# circuit.net
KiCad netlist of a schematic drawn in EAGLE
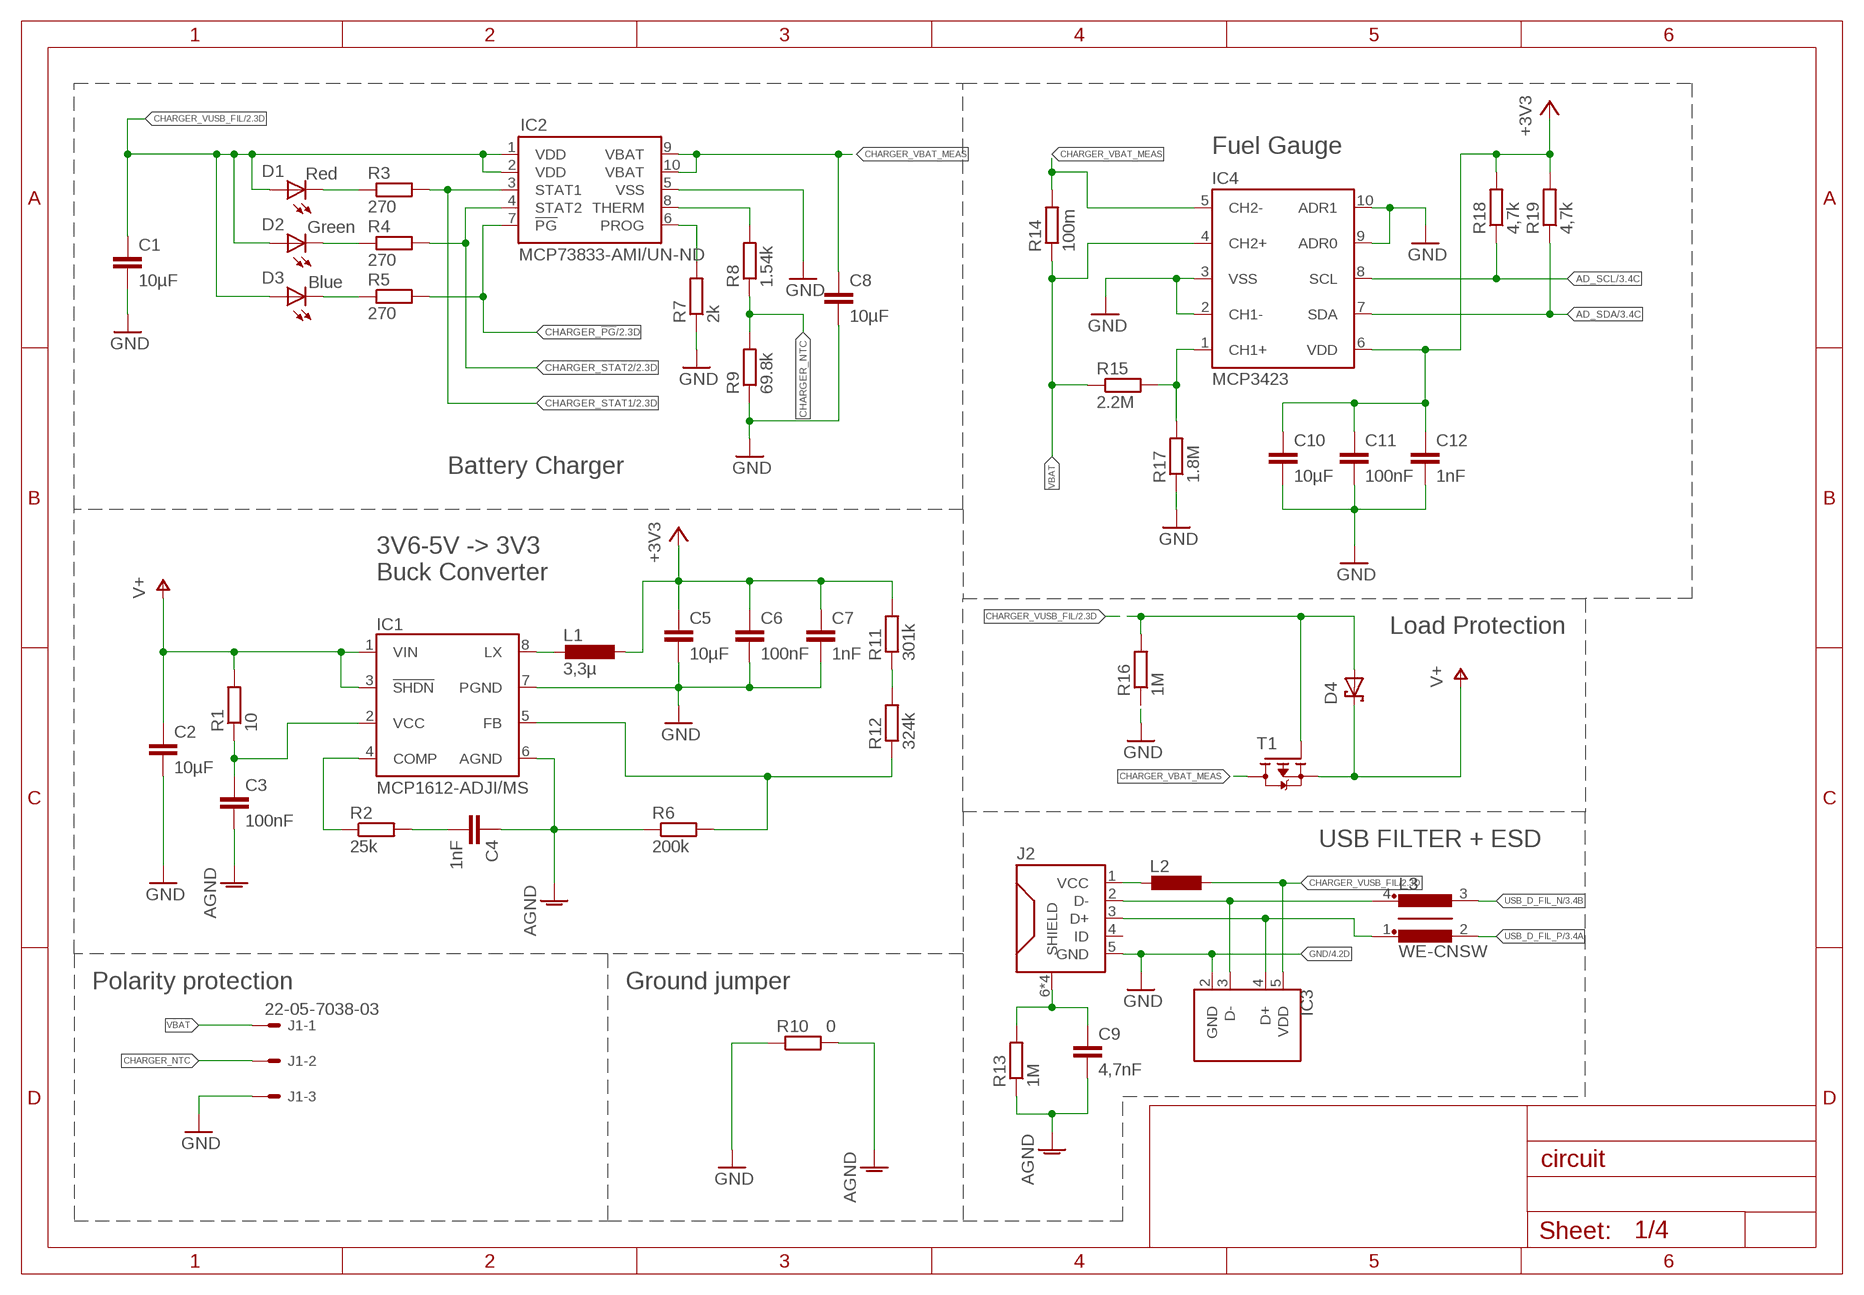
[diagram p0: schematic, sheet 1]
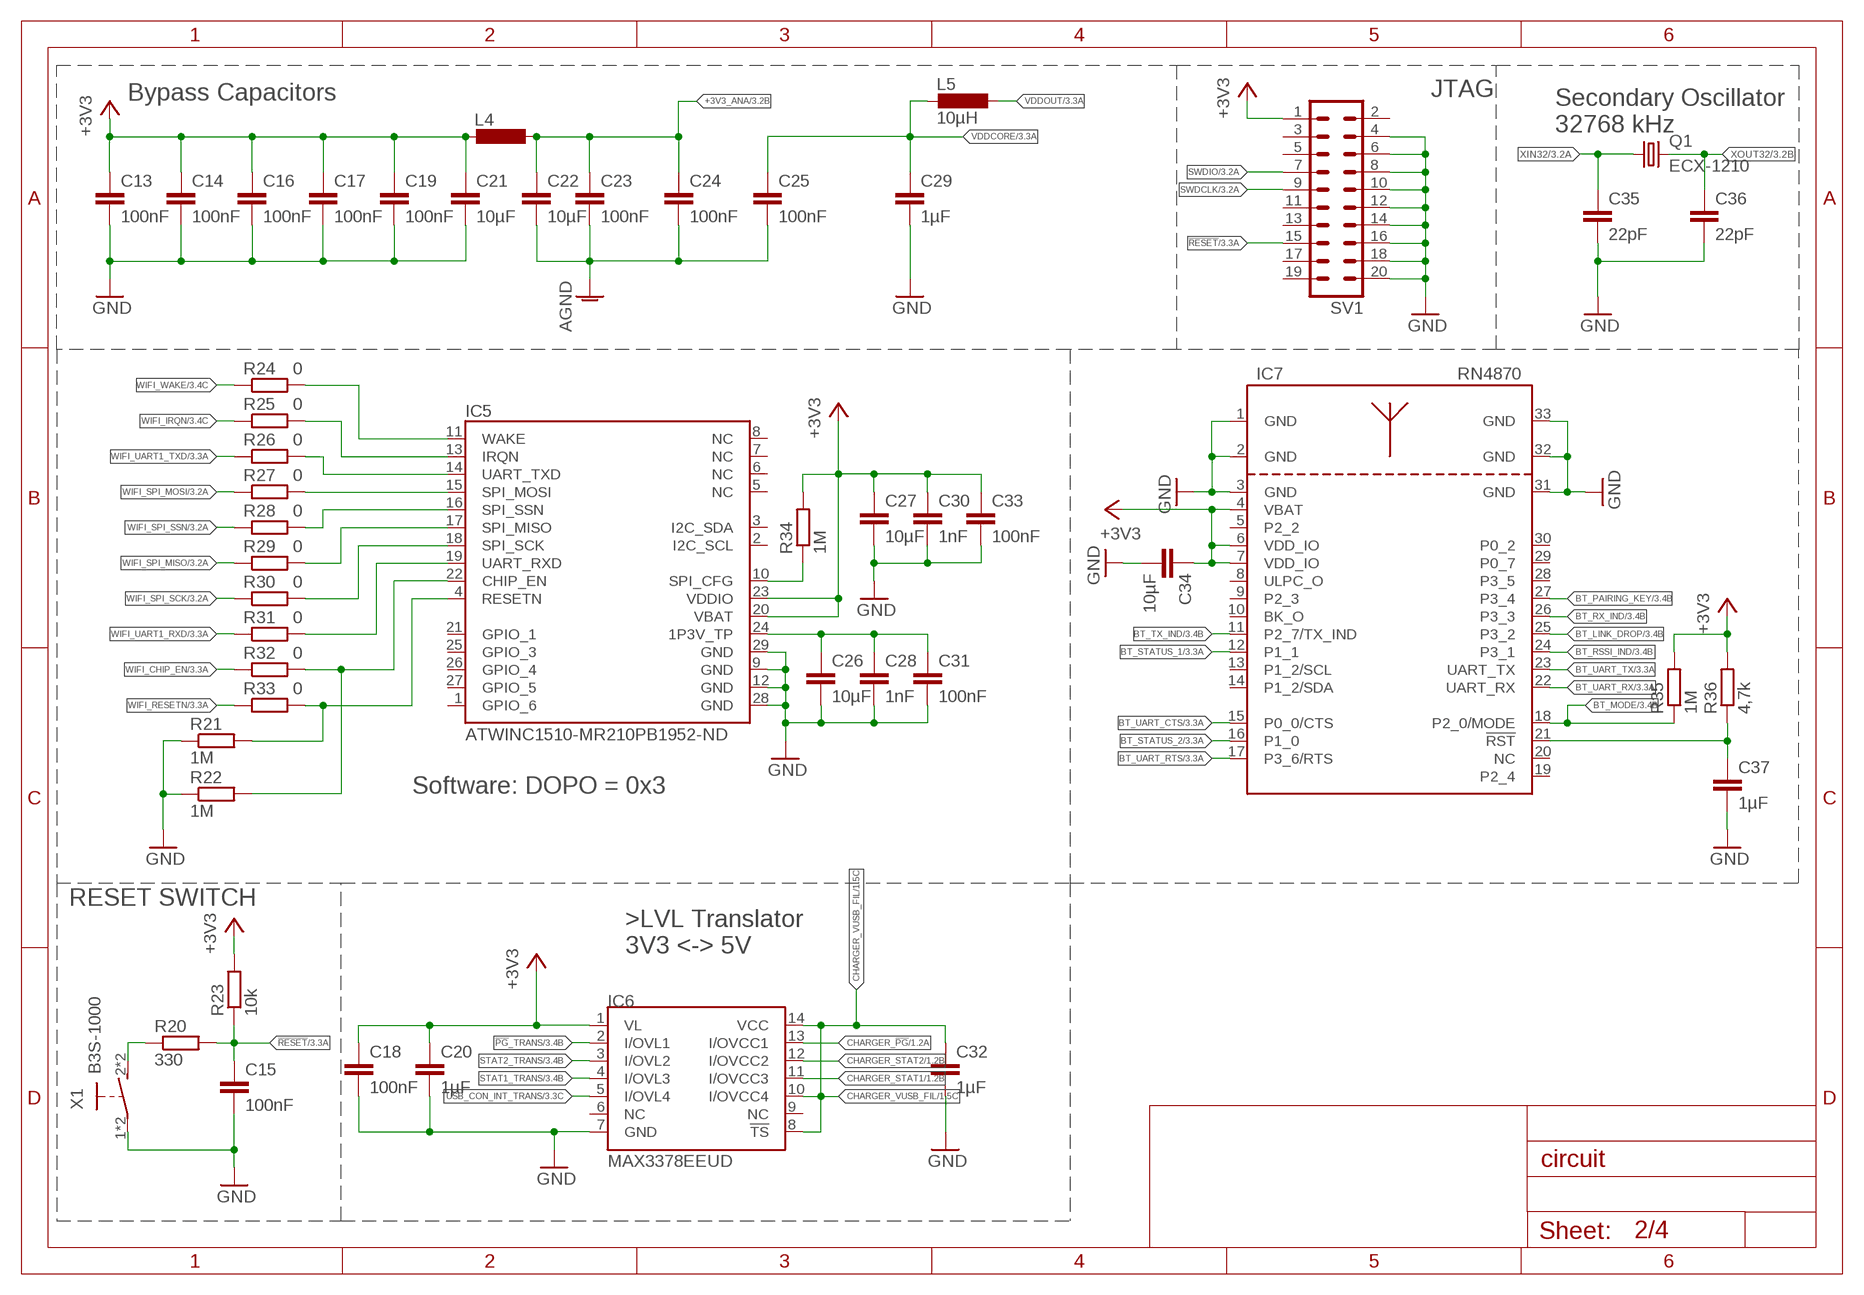
[diagram p1: schematic, sheet 2]
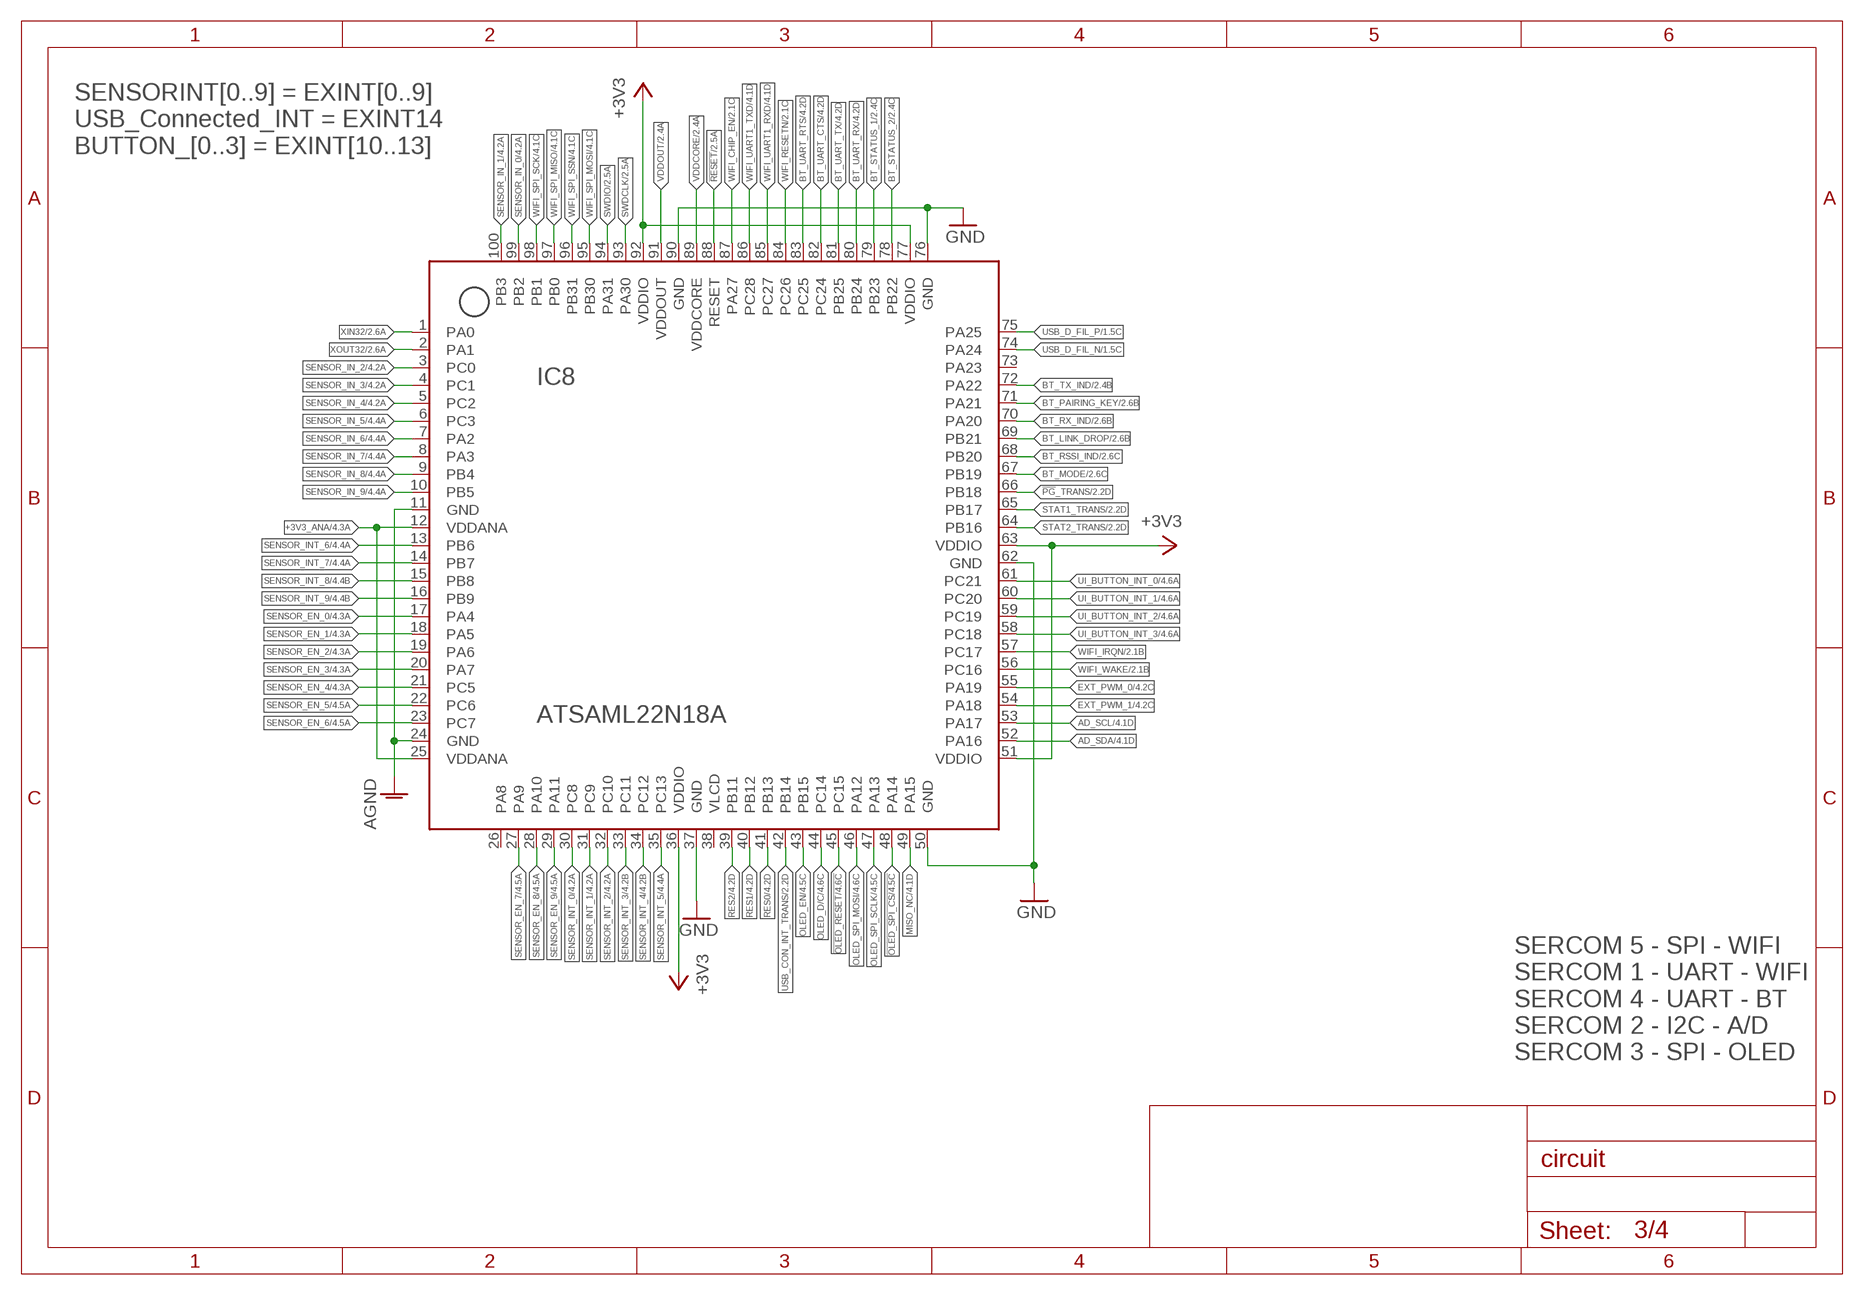
[diagram p2: schematic, sheet 3]
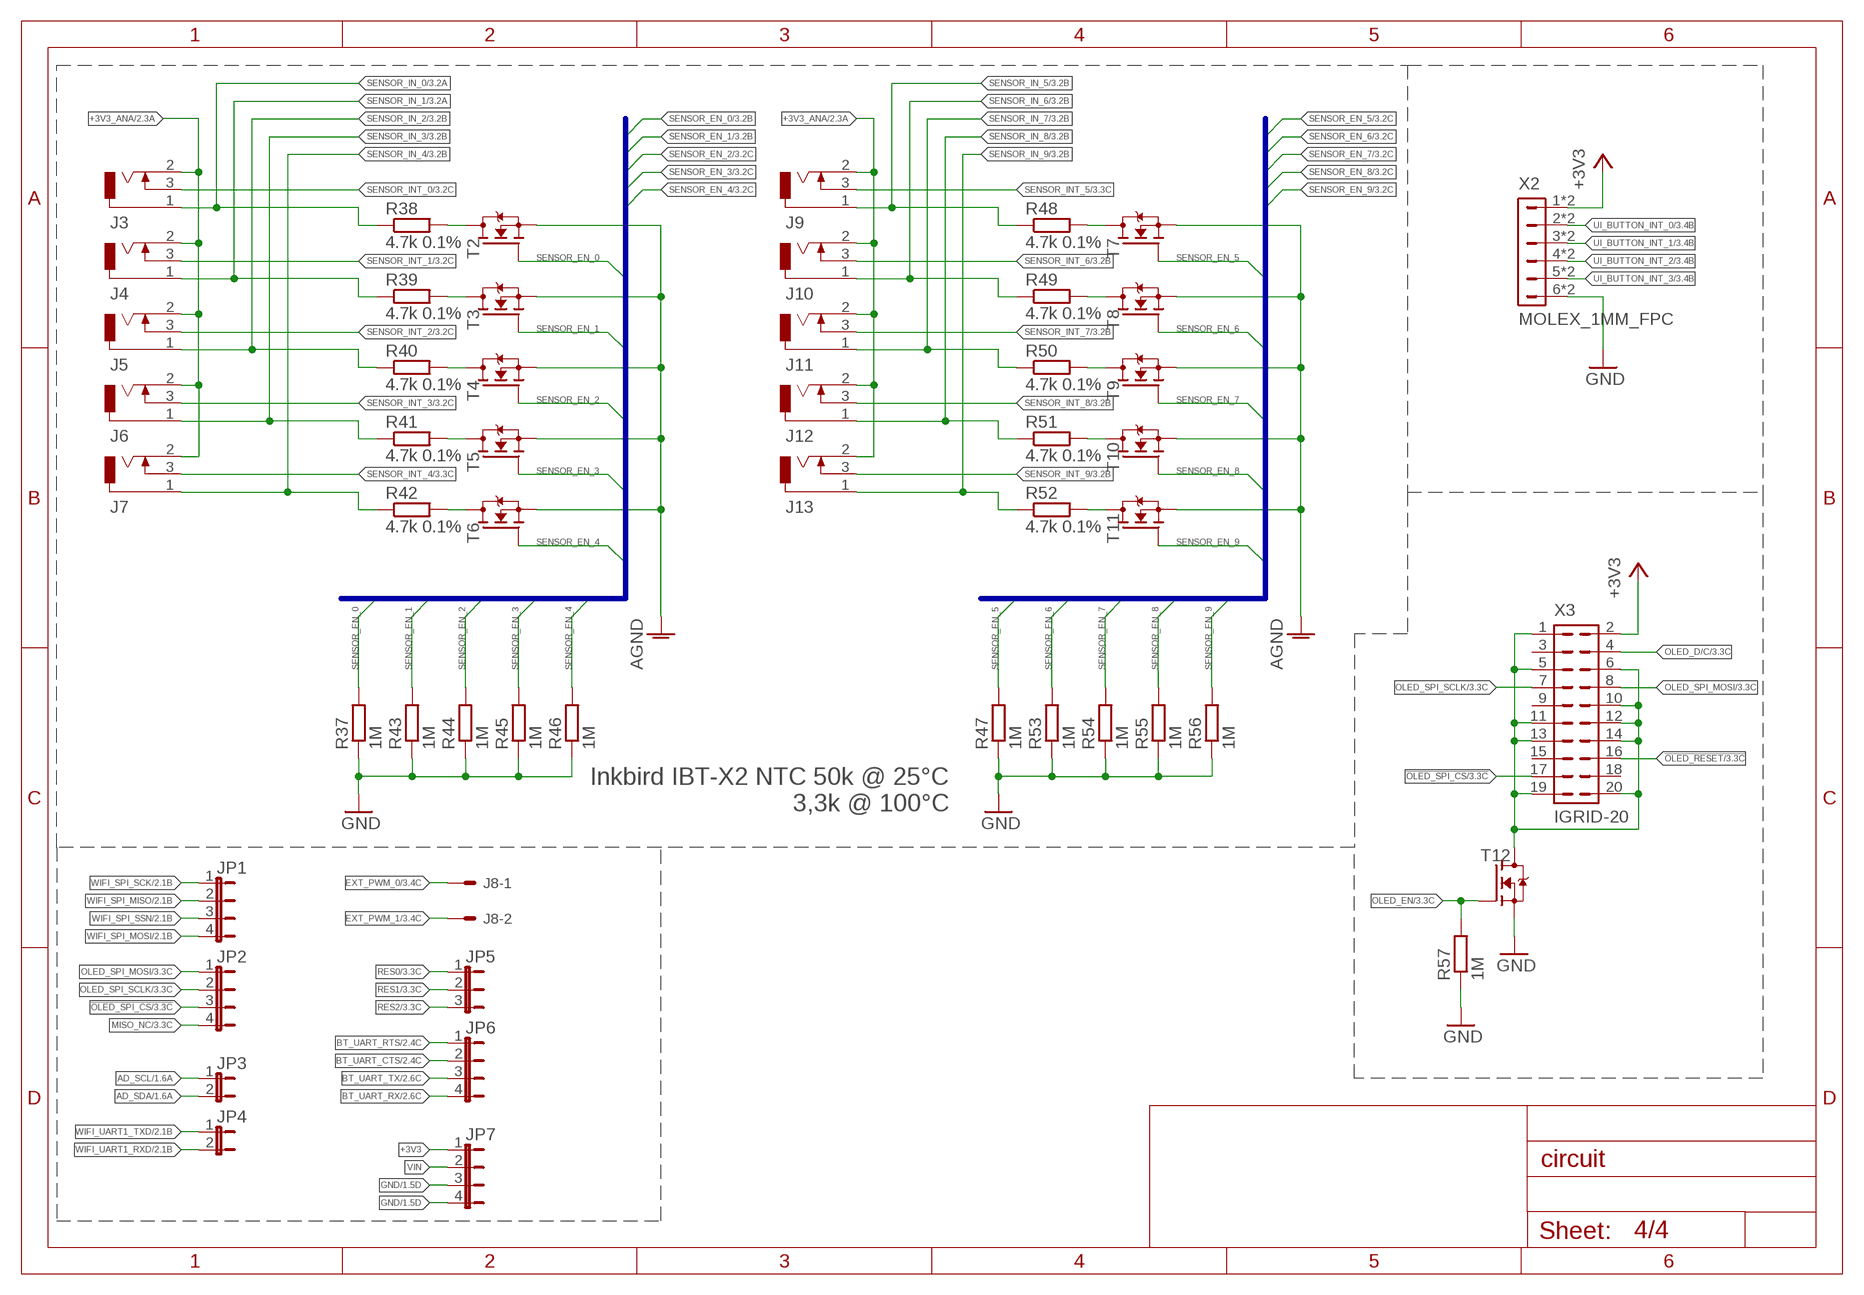
[diagram p3: schematic, sheet 4]

(export (version "E")
  (design (tool "Eeschema 10.0.6"))
  (components
    (comp (ref "J3")
      (value "2.5MM-AUDIO-JACK-MONO")
      (footprint "eagle-import:2.5MM-AUDIO-JACK-MONO")
      (libsource (lib "eagle-import") (part "2.5MM-AUDIO-JACK-MONO"))
    )
    (comp (ref "J4")
      (value "2.5MM-AUDIO-JACK-MONO")
      (footprint "eagle-import:2.5MM-AUDIO-JACK-MONO")
      (libsource (lib "eagle-import") (part "2.5MM-AUDIO-JACK-MONO"))
    )
    (comp (ref "J5")
      (value "2.5MM-AUDIO-JACK-MONO")
      (footprint "eagle-import:2.5MM-AUDIO-JACK-MONO")
      (libsource (lib "eagle-import") (part "2.5MM-AUDIO-JACK-MONO"))
    )
    (comp (ref "J6")
      (value "2.5MM-AUDIO-JACK-MONO")
      (footprint "eagle-import:2.5MM-AUDIO-JACK-MONO")
      (libsource (lib "eagle-import") (part "2.5MM-AUDIO-JACK-MONO"))
    )
    (comp (ref "J7")
      (value "2.5MM-AUDIO-JACK-MONO")
      (footprint "eagle-import:2.5MM-AUDIO-JACK-MONO")
      (libsource (lib "eagle-import") (part "2.5MM-AUDIO-JACK-MONO"))
    )
    (comp (ref "J8")
      (value "22-05-7028-02")
      (footprint "eagle-import:7395-02")
      (fields (field (name "OC_MOUSER") "538-22-05-7028"))
      (libsource (lib "eagle-import") (part "22-?-0205-7028"))
    )
    (comp (ref "J9")
      (value "2.5MM-AUDIO-JACK-MONONO_DRILL")
      (footprint "eagle-import:2.5MM-AUDIO-JACK-MONO-2")
      (libsource (lib "eagle-import") (part "2.5MM-AUDIO-JACK-MONONO_DRILL"))
    )
    (comp (ref "J10")
      (value "2.5MM-AUDIO-JACK-MONONO_DRILL")
      (footprint "eagle-import:2.5MM-AUDIO-JACK-MONO-2")
      (libsource (lib "eagle-import") (part "2.5MM-AUDIO-JACK-MONONO_DRILL"))
    )
    (comp (ref "J11")
      (value "2.5MM-AUDIO-JACK-MONONO_DRILL")
      (footprint "eagle-import:2.5MM-AUDIO-JACK-MONO-2")
      (libsource (lib "eagle-import") (part "2.5MM-AUDIO-JACK-MONONO_DRILL"))
    )
    (comp (ref "J12")
      (value "2.5MM-AUDIO-JACK-MONONO_DRILL")
      (footprint "eagle-import:2.5MM-AUDIO-JACK-MONO-2")
      (libsource (lib "eagle-import") (part "2.5MM-AUDIO-JACK-MONONO_DRILL"))
    )
    (comp (ref "J13")
      (value "2.5MM-AUDIO-JACK-MONONO_DRILL")
      (footprint "eagle-import:2.5MM-AUDIO-JACK-MONO-2")
      (libsource (lib "eagle-import") (part "2.5MM-AUDIO-JACK-MONONO_DRILL"))
    )
    (comp (ref "JP1")
      (value "4")
      (footprint "eagle-import:JP4")
      (libsource (lib "eagle-import") (part "JP4E"))
    )
    (comp (ref "JP2")
      (value "4")
      (footprint "eagle-import:JP4")
      (libsource (lib "eagle-import") (part "JP4E"))
    )
    (comp (ref "JP3")
      (value "2")
      (footprint "eagle-import:JP1")
      (libsource (lib "eagle-import") (part "JP1E"))
    )
    (comp (ref "JP4")
      (value "2")
      (footprint "eagle-import:JP1")
      (libsource (lib "eagle-import") (part "JP1E"))
    )
    (comp (ref "JP5")
      (value "3")
      (footprint "eagle-import:JP2")
      (libsource (lib "eagle-import") (part "JP2E"))
    )
    (comp (ref "JP6")
      (value "4")
      (footprint "eagle-import:JP4")
      (libsource (lib "eagle-import") (part "JP4E"))
    )
    (comp (ref "JP7")
      (value "4")
      (footprint "eagle-import:JP4")
      (libsource (lib "eagle-import") (part "JP4E"))
    )
    (comp (ref "R37")
      (value "1M")
      (footprint "eagle-import:R0603")
      (libsource (lib "eagle-import") (part "R-EU_R0603"))
    )
    (comp (ref "R38")
      (value "4.7k 0.1%")
      (footprint "eagle-import:R0603")
      (libsource (lib "eagle-import") (part "R-EU_R0603"))
    )
    (comp (ref "R39")
      (value "4.7k 0.1%")
      (footprint "eagle-import:R0603")
      (libsource (lib "eagle-import") (part "R-EU_R0603"))
    )
    (comp (ref "R40")
      (value "4.7k 0.1%")
      (footprint "eagle-import:R0603")
      (libsource (lib "eagle-import") (part "R-EU_R0603"))
    )
    (comp (ref "R41")
      (value "4.7k 0.1%")
      (footprint "eagle-import:R0603")
      (libsource (lib "eagle-import") (part "R-EU_R0603"))
    )
    (comp (ref "R42")
      (value "4.7k 0.1%")
      (footprint "eagle-import:R0603")
      (libsource (lib "eagle-import") (part "R-EU_R0603"))
    )
    (comp (ref "R43")
      (value "1M")
      (footprint "eagle-import:R0603")
      (libsource (lib "eagle-import") (part "R-EU_R0603"))
    )
    (comp (ref "R44")
      (value "1M")
      (footprint "eagle-import:R0603")
      (libsource (lib "eagle-import") (part "R-EU_R0603"))
    )
    (comp (ref "R45")
      (value "1M")
      (footprint "eagle-import:R0603")
      (libsource (lib "eagle-import") (part "R-EU_R0603"))
    )
    (comp (ref "R46")
      (value "1M")
      (footprint "eagle-import:R0603")
      (libsource (lib "eagle-import") (part "R-EU_R0603"))
    )
    (comp (ref "R47")
      (value "1M")
      (footprint "eagle-import:R0603")
      (libsource (lib "eagle-import") (part "R-EU_R0603"))
    )
    (comp (ref "R48")
      (value "4.7k 0.1%")
      (footprint "eagle-import:R0603")
      (libsource (lib "eagle-import") (part "R-EU_R0603"))
    )
    (comp (ref "R49")
      (value "4.7k 0.1%")
      (footprint "eagle-import:R0603")
      (libsource (lib "eagle-import") (part "R-EU_R0603"))
    )
    (comp (ref "R50")
      (value "4.7k 0.1%")
      (footprint "eagle-import:R0603")
      (libsource (lib "eagle-import") (part "R-EU_R0603"))
    )
    (comp (ref "R51")
      (value "4.7k 0.1%")
      (footprint "eagle-import:R0603")
      (libsource (lib "eagle-import") (part "R-EU_R0603"))
    )
    (comp (ref "R52")
      (value "4.7k 0.1%")
      (footprint "eagle-import:R0603")
      (libsource (lib "eagle-import") (part "R-EU_R0603"))
    )
    (comp (ref "R53")
      (value "1M")
      (footprint "eagle-import:R0603")
      (libsource (lib "eagle-import") (part "R-EU_R0603"))
    )
    (comp (ref "R54")
      (value "1M")
      (footprint "eagle-import:R0603")
      (libsource (lib "eagle-import") (part "R-EU_R0603"))
    )
    (comp (ref "R55")
      (value "1M")
      (footprint "eagle-import:R0603")
      (libsource (lib "eagle-import") (part "R-EU_R0603"))
    )
    (comp (ref "R56")
      (value "1M")
      (footprint "eagle-import:R0603")
      (libsource (lib "eagle-import") (part "R-EU_R0603"))
    )
    (comp (ref "R57")
      (value "1M")
      (footprint "eagle-import:R0603")
      (libsource (lib "eagle-import") (part "R-EU_R0603"))
    )
    (comp (ref "T2")
      (value "NMOSSOT323")
      (footprint "eagle-import:SOT-323")
      (libsource (lib "eagle-import") (part "NMOSSOT323"))
    )
    (comp (ref "T3")
      (value "NMOSSOT323")
      (footprint "eagle-import:SOT-323")
      (libsource (lib "eagle-import") (part "NMOSSOT323"))
    )
    (comp (ref "T4")
      (value "NMOSSOT323")
      (footprint "eagle-import:SOT-323")
      (libsource (lib "eagle-import") (part "NMOSSOT323"))
    )
    (comp (ref "T5")
      (value "NMOSSOT323")
      (footprint "eagle-import:SOT-323")
      (libsource (lib "eagle-import") (part "NMOSSOT323"))
    )
    (comp (ref "T6")
      (value "NMOSSOT323")
      (footprint "eagle-import:SOT-323")
      (libsource (lib "eagle-import") (part "NMOSSOT323"))
    )
    (comp (ref "T7")
      (value "NMOSSOT323")
      (footprint "eagle-import:SOT-323")
      (libsource (lib "eagle-import") (part "NMOSSOT323"))
    )
    (comp (ref "T8")
      (value "NMOSSOT323")
      (footprint "eagle-import:SOT-323")
      (libsource (lib "eagle-import") (part "NMOSSOT323"))
    )
    (comp (ref "T9")
      (value "NMOSSOT323")
      (footprint "eagle-import:SOT-323")
      (libsource (lib "eagle-import") (part "NMOSSOT323"))
    )
    (comp (ref "T10")
      (value "NMOSSOT323")
      (footprint "eagle-import:SOT-323")
      (libsource (lib "eagle-import") (part "NMOSSOT323"))
    )
    (comp (ref "T11")
      (value "NMOSSOT323")
      (footprint "eagle-import:SOT-323")
      (libsource (lib "eagle-import") (part "NMOSSOT323"))
    )
    (comp (ref "T12")
      (value "NMOSSOT323")
      (footprint "eagle-import:SOT-323")
      (libsource (lib "eagle-import") (part "NMOSSOT323"))
    )
    (comp (ref "X2")
      (value "MOLEX_1MM_FPC")
      (footprint "eagle-import:1MM_FPC_ZIF")
      (libsource (lib "eagle-import") (part "MOLEX_1MM_FPC"))
    )
    (comp (ref "X3")
      (value "IGRID-20")
      (footprint "eagle-import:I-GRID-20")
      (libsource (lib "eagle-import") (part "IGRID-20"))
    )
    (comp (ref "C13")
      (value "100nF")
      (footprint "eagle-import:C0603")
      (libsource (lib "eagle-import") (part "C-EUC0603"))
    )
    (comp (ref "C14")
      (value "100nF")
      (footprint "eagle-import:C0603")
      (libsource (lib "eagle-import") (part "C-EUC0603"))
    )
    (comp (ref "C15")
      (value "100nF")
      (footprint "eagle-import:C0603")
      (libsource (lib "eagle-import") (part "C-EUC0603"))
    )
    (comp (ref "C16")
      (value "100nF")
      (footprint "eagle-import:C0603")
      (libsource (lib "eagle-import") (part "C-EUC0603"))
    )
    (comp (ref "C17")
      (value "100nF")
      (footprint "eagle-import:C0603")
      (libsource (lib "eagle-import") (part "C-EUC0603"))
    )
    (comp (ref "C18")
      (value "100nF")
      (footprint "eagle-import:C0603")
      (libsource (lib "eagle-import") (part "C-EUC0603"))
    )
    (comp (ref "C19")
      (value "100nF")
      (footprint "eagle-import:C0603")
      (libsource (lib "eagle-import") (part "C-EUC0603"))
    )
    (comp (ref "C20")
      (value "1µF")
      (footprint "eagle-import:C0603")
      (libsource (lib "eagle-import") (part "C-EUC0603"))
    )
    (comp (ref "C21")
      (value "10µF")
      (footprint "eagle-import:C0805")
      (libsource (lib "eagle-import") (part "C-EUC0805"))
    )
    (comp (ref "C22")
      (value "10µF")
      (footprint "eagle-import:C0805")
      (libsource (lib "eagle-import") (part "C-EUC0805"))
    )
    (comp (ref "C23")
      (value "100nF")
      (footprint "eagle-import:C0603")
      (libsource (lib "eagle-import") (part "C-EUC0603"))
    )
    (comp (ref "C24")
      (value "100nF")
      (footprint "eagle-import:C0603")
      (libsource (lib "eagle-import") (part "C-EUC0603"))
    )
    (comp (ref "C25")
      (value "100nF")
      (footprint "eagle-import:C0603")
      (libsource (lib "eagle-import") (part "C-EUC0603"))
    )
    (comp (ref "C26")
      (value "10µF")
      (footprint "eagle-import:C0805")
      (libsource (lib "eagle-import") (part "C-EUC0805"))
    )
    (comp (ref "C27")
      (value "10µF")
      (footprint "eagle-import:C0805")
      (libsource (lib "eagle-import") (part "C-EUC0805"))
    )
    (comp (ref "C28")
      (value "1nF")
      (footprint "eagle-import:C0603")
      (libsource (lib "eagle-import") (part "C-EUC0603"))
    )
    (comp (ref "C29")
      (value "1µF")
      (footprint "eagle-import:C0603")
      (libsource (lib "eagle-import") (part "C-EUC0603"))
    )
    (comp (ref "C30")
      (value "1nF")
      (footprint "eagle-import:C0603")
      (libsource (lib "eagle-import") (part "C-EUC0603"))
    )
    (comp (ref "C31")
      (value "100nF")
      (footprint "eagle-import:C0603")
      (libsource (lib "eagle-import") (part "C-EUC0603"))
    )
    (comp (ref "C32")
      (value "1µF")
      (footprint "eagle-import:C0603")
      (libsource (lib "eagle-import") (part "C-EUC0603"))
    )
    (comp (ref "C33")
      (value "100nF")
      (footprint "eagle-import:C0603")
      (libsource (lib "eagle-import") (part "C-EUC0603"))
    )
    (comp (ref "C34")
      (value "10µF")
      (footprint "eagle-import:C0805")
      (libsource (lib "eagle-import") (part "C-EUC0805"))
    )
    (comp (ref "C35")
      (value "22pF")
      (footprint "eagle-import:C0603")
      (libsource (lib "eagle-import") (part "C-EUC0603"))
    )
    (comp (ref "C36")
      (value "22pF")
      (footprint "eagle-import:C0603")
      (libsource (lib "eagle-import") (part "C-EUC0603"))
    )
    (comp (ref "C37")
      (value "1µF")
      (footprint "eagle-import:C0603")
      (libsource (lib "eagle-import") (part "C-EUC0603"))
    )
    (comp (ref "IC5")
      (value "ATWINC1510-MR210PB1952-ND")
      (footprint "eagle-import:ATWINC15X0-MODULE")
      (libsource (lib "eagle-import") (part "ATWINC1510-MR210PB1952-ND"))
    )
    (comp (ref "IC6")
      (value "MAX3378EEUD")
      (footprint "eagle-import:TSSOP14")
      (libsource (lib "eagle-import") (part "MAX3378EEUD"))
    )
    (comp (ref "IC7")
      (value "RN4870")
      (footprint "eagle-import:RN4870-MODULE")
      (libsource (lib "eagle-import") (part "RN4870"))
    )
    (comp (ref "L4")
      (value "L-0603")
      (footprint "eagle-import:L0603")
      (libsource (lib "eagle-import") (part "L-0603"))
    )
    (comp (ref "L5")
      (value "10µH")
      (footprint "eagle-import:L-1210")
      (libsource (lib "eagle-import") (part "L-1210"))
    )
    (comp (ref "Q1")
      (value "ECX-1210")
      (footprint "eagle-import:ECX-1210")
      (libsource (lib "eagle-import") (part "ECX-1210"))
    )
    (comp (ref "R20")
      (value "330")
      (footprint "eagle-import:R0603")
      (libsource (lib "eagle-import") (part "R-EU_R0603"))
    )
    (comp (ref "R21")
      (value "1M")
      (footprint "eagle-import:R0603")
      (libsource (lib "eagle-import") (part "R-EU_R0603"))
    )
    (comp (ref "R22")
      (value "1M")
      (footprint "eagle-import:R0603")
      (libsource (lib "eagle-import") (part "R-EU_R0603"))
    )
    (comp (ref "R23")
      (value "10k")
      (footprint "eagle-import:R0603")
      (libsource (lib "eagle-import") (part "R-EU_R0603"))
    )
    (comp (ref "R24")
      (value "0")
      (footprint "eagle-import:R0603")
      (libsource (lib "eagle-import") (part "R-EU_R0603"))
    )
    (comp (ref "R25")
      (value "0")
      (footprint "eagle-import:R0603")
      (libsource (lib "eagle-import") (part "R-EU_R0603"))
    )
    (comp (ref "R26")
      (value "0")
      (footprint "eagle-import:R0603")
      (libsource (lib "eagle-import") (part "R-EU_R0603"))
    )
    (comp (ref "R27")
      (value "0")
      (footprint "eagle-import:R0603")
      (libsource (lib "eagle-import") (part "R-EU_R0603"))
    )
    (comp (ref "R28")
      (value "0")
      (footprint "eagle-import:R0603")
      (libsource (lib "eagle-import") (part "R-EU_R0603"))
    )
    (comp (ref "R29")
      (value "0")
      (footprint "eagle-import:R0603")
      (libsource (lib "eagle-import") (part "R-EU_R0603"))
    )
    (comp (ref "R30")
      (value "0")
      (footprint "eagle-import:R0603")
      (libsource (lib "eagle-import") (part "R-EU_R0603"))
    )
    (comp (ref "R31")
      (value "0")
      (footprint "eagle-import:R0603")
      (libsource (lib "eagle-import") (part "R-EU_R0603"))
    )
    (comp (ref "R32")
      (value "0")
      (footprint "eagle-import:R0603")
      (libsource (lib "eagle-import") (part "R-EU_R0603"))
    )
    (comp (ref "R33")
      (value "0")
      (footprint "eagle-import:R0603")
      (libsource (lib "eagle-import") (part "R-EU_R0603"))
    )
    (comp (ref "R34")
      (value "1M")
      (footprint "eagle-import:R0603")
      (libsource (lib "eagle-import") (part "R-EU_R0603"))
    )
    (comp (ref "R35")
      (value "1M")
      (footprint "eagle-import:R0603")
      (libsource (lib "eagle-import") (part "R-EU_R0603"))
    )
    (comp (ref "R36")
      (value "4,7k")
      (footprint "eagle-import:R0603")
      (libsource (lib "eagle-import") (part "R-EU_R0603"))
    )
    (comp (ref "SV1")
      (value "JTAGEDU")
      (footprint "eagle-import:ML20")
      (libsource (lib "eagle-import") (part "ML20"))
    )
    (comp (ref "X1")
      (value "B3S-1000")
      (footprint "eagle-import:B3S")
      (libsource (lib "eagle-import") (part "B3S-1000"))
    )
    (comp (ref "IC8")
      (value "ATSAML22N18A")
      (footprint "eagle-import:TQFP100")
      (libsource (lib "eagle-import") (part "ATSAML22N18A"))
    )
    (comp (ref "C1")
      (value "10µF")
      (footprint "eagle-import:C0805")
      (libsource (lib "eagle-import") (part "C-EUC0805"))
    )
    (comp (ref "C2")
      (value "10µF")
      (footprint "eagle-import:C0805")
      (libsource (lib "eagle-import") (part "C-EUC0805"))
    )
    (comp (ref "C3")
      (value "100nF")
      (footprint "eagle-import:C0603")
      (libsource (lib "eagle-import") (part "C-EUC0603"))
    )
    (comp (ref "C4")
      (value "1nF")
      (footprint "eagle-import:C0603")
      (libsource (lib "eagle-import") (part "C-EUC0603"))
    )
    (comp (ref "C5")
      (value "10µF")
      (footprint "eagle-import:C0805")
      (libsource (lib "eagle-import") (part "C-EUC0805"))
    )
    (comp (ref "C6")
      (value "100nF")
      (footprint "eagle-import:C0603")
      (libsource (lib "eagle-import") (part "C-EUC0603"))
    )
    (comp (ref "C7")
      (value "1nF")
      (footprint "eagle-import:C0603")
      (libsource (lib "eagle-import") (part "C-EUC0603"))
    )
    (comp (ref "C8")
      (value "10µF")
      (footprint "eagle-import:C0805")
      (libsource (lib "eagle-import") (part "C-EUC0805"))
    )
    (comp (ref "C9")
      (value "4,7nF")
      (footprint "eagle-import:C0603")
      (libsource (lib "eagle-import") (part "C-EUC0603"))
    )
    (comp (ref "C10")
      (value "10µF")
      (footprint "eagle-import:C0805")
      (libsource (lib "eagle-import") (part "C-EUC0805"))
    )
    (comp (ref "C11")
      (value "100nF")
      (footprint "eagle-import:C0603")
      (libsource (lib "eagle-import") (part "C-EUC0603"))
    )
    (comp (ref "C12")
      (value "1nF")
      (footprint "eagle-import:C0603")
      (libsource (lib "eagle-import") (part "C-EUC0603"))
    )
    (comp (ref "D1")
      (value "Red")
      (footprint "eagle-import:LED_2012")
      (libsource (lib "eagle-import") (part "LED-2012"))
    )
    (comp (ref "D2")
      (value "Green")
      (footprint "eagle-import:LED_2012")
      (libsource (lib "eagle-import") (part "LED-2012"))
    )
    (comp (ref "D3")
      (value "Blue")
      (footprint "eagle-import:LED_2012")
      (libsource (lib "eagle-import") (part "LED-2012"))
    )
    (comp (ref "D4")
      (value "BAT60AE6327HTSA1")
      (footprint "eagle-import:SOD323")
      (libsource (lib "eagle-import") (part "BAT60AE6327HTSA1"))
    )
    (comp (ref "IC1")
      (value "MCP1612-ADJI/MS")
      (footprint "eagle-import:MSOP8")
      (libsource (lib "eagle-import") (part "MCP1612-ADJI/MS"))
    )
    (comp (ref "IC2")
      (value "MCP73833-AMI/UN-ND")
      (footprint "eagle-import:MSOP10")
      (libsource (lib "eagle-import") (part "MCP73833-AMI/UN-ND"))
    )
    (comp (ref "IC3")
      (value "WE-TVS")
      (footprint "eagle-import:SOT23-5L")
      (libsource (lib "eagle-import") (part "WE-TVS"))
    )
    (comp (ref "IC4")
      (value "MCP3423")
      (footprint "eagle-import:MSOP10")
      (libsource (lib "eagle-import") (part "MCP3423"))
    )
    (comp (ref "J1")
      (value "22-05-7038-03")
      (footprint "eagle-import:7395-03")
      (libsource (lib "eagle-import") (part "22-?-0305-7038"))
    )
    (comp (ref "J2")
      (value "USB2-MICRO")
      (footprint "eagle-import:USB-2-MICRO")
      (libsource (lib "eagle-import") (part "USB2-MICRO"))
    )
    (comp (ref "L1")
      (value "3,3µ")
      (footprint "eagle-import:WE-LHMI")
      (libsource (lib "eagle-import") (part "WE-LHMI"))
    )
    (comp (ref "L2")
      (value "L-0603")
      (footprint "eagle-import:L0603")
      (libsource (lib "eagle-import") (part "L-0603"))
    )
    (comp (ref "L3")
      (value "WE-CNSW")
      (footprint "eagle-import:WE-CNSW")
      (libsource (lib "eagle-import") (part "WE-CNSW"))
    )
    (comp (ref "R1")
      (value "10")
      (footprint "eagle-import:R0603")
      (libsource (lib "eagle-import") (part "R-EU_R0603"))
    )
    (comp (ref "R2")
      (value "25k")
      (footprint "eagle-import:R0805")
      (libsource (lib "eagle-import") (part "R-EU_R0805"))
    )
    (comp (ref "R3")
      (value "270")
      (footprint "eagle-import:R0603")
      (libsource (lib "eagle-import") (part "R-EU_R0603"))
    )
    (comp (ref "R4")
      (value "270")
      (footprint "eagle-import:R0603")
      (libsource (lib "eagle-import") (part "R-EU_R0603"))
    )
    (comp (ref "R5")
      (value "270")
      (footprint "eagle-import:R0603")
      (libsource (lib "eagle-import") (part "R-EU_R0603"))
    )
    (comp (ref "R6")
      (value "200k")
      (footprint "eagle-import:R0603")
      (libsource (lib "eagle-import") (part "R-EU_R0603"))
    )
    (comp (ref "R7")
      (value "2k")
      (footprint "eagle-import:R0603")
      (libsource (lib "eagle-import") (part "R-EU_R0603"))
    )
    (comp (ref "R8")
      (value "1.54k")
      (footprint "eagle-import:R0603")
      (libsource (lib "eagle-import") (part "R-EU_R0603"))
    )
    (comp (ref "R9")
      (value "69.8k")
      (footprint "eagle-import:R0603")
      (libsource (lib "eagle-import") (part "R-EU_R0603"))
    )
    (comp (ref "R10")
      (value "0")
      (footprint "eagle-import:R0603")
      (libsource (lib "eagle-import") (part "R-EU_R0603"))
    )
    (comp (ref "R11")
      (value "301k")
      (footprint "eagle-import:R0603")
      (libsource (lib "eagle-import") (part "R-EU_R0603"))
    )
    (comp (ref "R12")
      (value "324k")
      (footprint "eagle-import:R0603")
      (libsource (lib "eagle-import") (part "R-EU_R0603"))
    )
    (comp (ref "R13")
      (value "1M")
      (footprint "eagle-import:R0603")
      (libsource (lib "eagle-import") (part "R-EU_R0603"))
    )
    (comp (ref "R14")
      (value "100m")
      (footprint "eagle-import:R5025")
      (libsource (lib "eagle-import") (part "R-EU_R5025"))
    )
    (comp (ref "R15")
      (value "2.2M")
      (footprint "eagle-import:R0603")
      (libsource (lib "eagle-import") (part "R-EU_R0603"))
    )
    (comp (ref "R16")
      (value "1M")
      (footprint "eagle-import:R0603")
      (libsource (lib "eagle-import") (part "R-EU_R0603"))
    )
    (comp (ref "R17")
      (value "1.8M")
      (footprint "eagle-import:R0603")
      (libsource (lib "eagle-import") (part "R-EU_R0603"))
    )
    (comp (ref "R18")
      (value "4,7k")
      (footprint "eagle-import:R0603")
      (libsource (lib "eagle-import") (part "R-EU_R0603"))
    )
    (comp (ref "R19")
      (value "4,7k")
      (footprint "eagle-import:R0603")
      (libsource (lib "eagle-import") (part "R-EU_R0603"))
    )
    (comp (ref "T1")
      (value "PMOS")
      (footprint "eagle-import:SOT23")
      (libsource (lib "eagle-import") (part "PMOS"))
    )
  )
  (nets
    (net (code "1") (name "+3V3") (class "Default")
      (node (ref "C10") (pin "1") (pinfunction "1_1") (pintype "passive"))
      (node (ref "C11") (pin "1") (pinfunction "1_1") (pintype "passive"))
      (node (ref "C12") (pin "1") (pinfunction "1_1") (pintype "passive"))
      (node (ref "C13") (pin "1") (pinfunction "1_1") (pintype "passive"))
      (node (ref "C14") (pin "1") (pinfunction "1_1") (pintype "passive"))
      (node (ref "C16") (pin "1") (pinfunction "1_1") (pintype "passive"))
      (node (ref "C17") (pin "1") (pinfunction "1_1") (pintype "passive"))
      (node (ref "C18") (pin "1") (pinfunction "1_1") (pintype "passive"))
      (node (ref "C19") (pin "1") (pinfunction "1_1") (pintype "passive"))
      (node (ref "C20") (pin "1") (pinfunction "1_1") (pintype "passive"))
      (node (ref "C21") (pin "1") (pinfunction "1_1") (pintype "passive"))
      (node (ref "C27") (pin "1") (pinfunction "1_1") (pintype "passive"))
      (node (ref "C30") (pin "1") (pinfunction "1_1") (pintype "passive"))
      (node (ref "C33") (pin "1") (pinfunction "1_1") (pintype "passive"))
      (node (ref "C34") (pin "1") (pinfunction "1_1") (pintype "passive"))
      (node (ref "C5") (pin "1") (pinfunction "1_1") (pintype "passive"))
      (node (ref "C6") (pin "1") (pinfunction "1_1") (pintype "passive"))
      (node (ref "C7") (pin "1") (pinfunction "1_1") (pintype "passive"))
      (node (ref "IC4") (pin "6") (pinfunction "VDD_6") (pintype "bidirectional"))
      (node (ref "IC5") (pin "20") (pinfunction "VBAT_20") (pintype "bidirectional"))
      (node (ref "IC5") (pin "23") (pinfunction "VDDIO_23") (pintype "bidirectional"))
      (node (ref "IC6") (pin "1") (pinfunction "VL_1") (pintype "bidirectional"))
      (node (ref "IC7") (pin "4") (pinfunction "VBAT_4") (pintype "bidirectional"))
      (node (ref "IC7") (pin "6") (pinfunction "VDD_IO_6") (pintype "bidirectional"))
      (node (ref "IC7") (pin "7") (pinfunction "VDD_IO_7") (pintype "bidirectional"))
      (node (ref "IC8") (pin "36") (pinfunction "VDDIO_36") (pintype "bidirectional"))
      (node (ref "IC8") (pin "51") (pinfunction "VDDIO_51") (pintype "bidirectional"))
      (node (ref "IC8") (pin "63") (pinfunction "VDDIO_63") (pintype "bidirectional"))
      (node (ref "IC8") (pin "77") (pinfunction "VDDIO_77") (pintype "bidirectional"))
      (node (ref "IC8") (pin "92") (pinfunction "VDDIO_92") (pintype "bidirectional"))
      (node (ref "JP7") (pin "1") (pinfunction "1_1") (pintype "passive"))
      (node (ref "L1") (pin "1") (pinfunction "1_1") (pintype "passive"))
      (node (ref "L4") (pin "2") (pinfunction "2_2") (pintype "passive"))
      (node (ref "R11") (pin "2") (pinfunction "2_2") (pintype "passive"))
      (node (ref "R18") (pin "2") (pinfunction "2_2") (pintype "passive"))
      (node (ref "R19") (pin "2") (pinfunction "2_2") (pintype "passive"))
      (node (ref "R23") (pin "2") (pinfunction "2_2") (pintype "passive"))
      (node (ref "R34") (pin "2") (pinfunction "2_2") (pintype "passive"))
      (node (ref "R35") (pin "2") (pinfunction "2_2") (pintype "passive"))
      (node (ref "R36") (pin "2") (pinfunction "2_2") (pintype "passive"))
      (node (ref "SV1") (pin "1") (pinfunction "1_1") (pintype "passive"))
      (node (ref "X2") (pin "1") (pinfunction "1_1") (pintype "passive"))
      (node (ref "X2") (pin "7") (pinfunction "1_7") (pintype "passive"))
      (node (ref "X3") (pin "2") (pinfunction "2_2") (pintype "passive"))
    )
    (net (code "2") (name "+3V3_ANA") (class "Default")
      (node (ref "C22") (pin "1") (pinfunction "1_1") (pintype "passive"))
      (node (ref "C23") (pin "1") (pinfunction "1_1") (pintype "passive"))
      (node (ref "C24") (pin "1") (pinfunction "1_1") (pintype "passive"))
      (node (ref "IC8") (pin "12") (pinfunction "VDDANA_12") (pintype "bidirectional"))
      (node (ref "IC8") (pin "25") (pinfunction "VDDANA_25") (pintype "bidirectional"))
      (node (ref "J10") (pin "2") (pinfunction "2_2") (pintype "passive"))
      (node (ref "J11") (pin "2") (pinfunction "2_2") (pintype "passive"))
      (node (ref "J12") (pin "2") (pinfunction "2_2") (pintype "passive"))
      (node (ref "J13") (pin "2") (pinfunction "2_2") (pintype "passive"))
      (node (ref "J3") (pin "2") (pinfunction "2_2") (pintype "passive"))
      (node (ref "J4") (pin "2") (pinfunction "2_2") (pintype "passive"))
      (node (ref "J5") (pin "2") (pinfunction "2_2") (pintype "passive"))
      (node (ref "J6") (pin "2") (pinfunction "2_2") (pintype "passive"))
      (node (ref "J7") (pin "2") (pinfunction "2_2") (pintype "passive"))
      (node (ref "J9") (pin "2") (pinfunction "2_2") (pintype "passive"))
      (node (ref "L4") (pin "1") (pinfunction "1_1") (pintype "passive"))
    )
    (net (code "3") (name "AD_SCL") (class "Default")
      (node (ref "IC4") (pin "8") (pinfunction "SCL_8") (pintype "bidirectional"))
      (node (ref "IC8") (pin "53") (pinfunction "PA17_53") (pintype "bidirectional"))
      (node (ref "JP3") (pin "1") (pinfunction "1_1") (pintype "passive"))
      (node (ref "R18") (pin "1") (pinfunction "1_1") (pintype "passive"))
    )
    (net (code "4") (name "AD_SDA") (class "Default")
      (node (ref "IC4") (pin "7") (pinfunction "SDA_7") (pintype "bidirectional"))
      (node (ref "IC8") (pin "52") (pinfunction "PA16_52") (pintype "bidirectional"))
      (node (ref "JP3") (pin "2") (pinfunction "2_2") (pintype "passive"))
      (node (ref "R19") (pin "1") (pinfunction "1_1") (pintype "passive"))
    )
    (net (code "5") (name "AGND") (class "Default")
      (node (ref "C22") (pin "2") (pinfunction "2_2") (pintype "passive"))
      (node (ref "C23") (pin "2") (pinfunction "2_2") (pintype "passive"))
      (node (ref "C24") (pin "2") (pinfunction "2_2") (pintype "passive"))
      (node (ref "C25") (pin "2") (pinfunction "2_2") (pintype "passive"))
      (node (ref "C3") (pin "2") (pinfunction "2_2") (pintype "passive"))
      (node (ref "C4") (pin "1") (pinfunction "1_1") (pintype "passive"))
      (node (ref "C9") (pin "2") (pinfunction "2_2") (pintype "passive"))
      (node (ref "IC1") (pin "6") (pinfunction "AGND_6") (pintype "bidirectional"))
      (node (ref "IC8") (pin "11") (pinfunction "GND_11") (pintype "power_in"))
      (node (ref "IC8") (pin "24") (pinfunction "GND_24") (pintype "power_in"))
      (node (ref "R10") (pin "2") (pinfunction "2_2") (pintype "passive"))
      (node (ref "R13") (pin "1") (pinfunction "1_1") (pintype "passive"))
      (node (ref "R6") (pin "1") (pinfunction "1_1") (pintype "passive"))
      (node (ref "T10") (pin "2") (pinfunction "S_2") (pintype "passive"))
      (node (ref "T11") (pin "2") (pinfunction "S_2") (pintype "passive"))
      (node (ref "T2") (pin "2") (pinfunction "S_2") (pintype "passive"))
      (node (ref "T3") (pin "2") (pinfunction "S_2") (pintype "passive"))
      (node (ref "T4") (pin "2") (pinfunction "S_2") (pintype "passive"))
      (node (ref "T5") (pin "2") (pinfunction "S_2") (pintype "passive"))
      (node (ref "T6") (pin "2") (pinfunction "S_2") (pintype "passive"))
      (node (ref "T7") (pin "2") (pinfunction "S_2") (pintype "passive"))
      (node (ref "T8") (pin "2") (pinfunction "S_2") (pintype "passive"))
      (node (ref "T9") (pin "2") (pinfunction "S_2") (pintype "passive"))
    )
    (net (code "6") (name "BT_LINK_DROP") (class "Default")
      (node (ref "IC7") (pin "25") (pinfunction "P3_2_25") (pintype "output"))
      (node (ref "IC8") (pin "69") (pinfunction "PB21_69") (pintype "bidirectional"))
    )
    (net (code "7") (name "BT_MODE") (class "Default")
      (node (ref "IC7") (pin "18") (pinfunction "P2_0/MODE_18") (pintype "bidirectional"))
      (node (ref "IC8") (pin "67") (pinfunction "PB19_67") (pintype "bidirectional"))
      (node (ref "R35") (pin "1") (pinfunction "1_1") (pintype "passive"))
    )
    (net (code "8") (name "BT_PAIRING_KEY") (class "Default")
      (node (ref "IC7") (pin "27") (pinfunction "P3_4_27") (pintype "output"))
      (node (ref "IC8") (pin "71") (pinfunction "PA21_71") (pintype "bidirectional"))
    )
    (net (code "9") (name "BT_RSSI_IND") (class "Default")
      (node (ref "IC7") (pin "24") (pinfunction "P3_1_24") (pintype "output"))
      (node (ref "IC8") (pin "68") (pinfunction "PB20_68") (pintype "bidirectional"))
    )
    (net (code "10") (name "BT_RX_IND") (class "Default")
      (node (ref "IC7") (pin "26") (pinfunction "P3_3_26") (pintype "output"))
      (node (ref "IC8") (pin "70") (pinfunction "PA20_70") (pintype "bidirectional"))
    )
    (net (code "11") (name "BT_STATUS_1") (class "Default")
      (node (ref "IC7") (pin "12") (pinfunction "P1_1_12") (pintype "bidirectional"))
      (node (ref "IC8") (pin "79") (pinfunction "PB23_79") (pintype "bidirectional"))
    )
    (net (code "12") (name "BT_STATUS_2") (class "Default")
      (node (ref "IC7") (pin "16") (pinfunction "P1_0_16") (pintype "bidirectional"))
      (node (ref "IC8") (pin "78") (pinfunction "PB22_78") (pintype "bidirectional"))
    )
    (net (code "13") (name "BT_TX_IND") (class "Default")
      (node (ref "IC7") (pin "11") (pinfunction "P2_7/TX_IND_11") (pintype "output"))
      (node (ref "IC8") (pin "72") (pinfunction "PA22_72") (pintype "bidirectional"))
    )
    (net (code "14") (name "BT_UART_CTS") (class "Default")
      (node (ref "IC7") (pin "15") (pinfunction "P0_0/CTS_15") (pintype "bidirectional"))
      (node (ref "IC8") (pin "82") (pinfunction "PC24_82") (pintype "bidirectional"))
      (node (ref "JP6") (pin "2") (pinfunction "2_2") (pintype "passive"))
    )
    (net (code "15") (name "BT_UART_RTS") (class "Default")
      (node (ref "IC7") (pin "17") (pinfunction "P3_6/RTS_17") (pintype "bidirectional"))
      (node (ref "IC8") (pin "83") (pinfunction "PC25_83") (pintype "bidirectional"))
      (node (ref "JP6") (pin "1") (pinfunction "1_1") (pintype "passive"))
    )
    (net (code "16") (name "BT_UART_RX") (class "Default")
      (node (ref "IC7") (pin "22") (pinfunction "UART_RX_22") (pintype "bidirectional"))
      (node (ref "IC8") (pin "80") (pinfunction "PB24_80") (pintype "bidirectional"))
      (node (ref "JP6") (pin "4") (pinfunction "4_4") (pintype "passive"))
    )
    (net (code "17") (name "BT_UART_TX") (class "Default")
      (node (ref "IC7") (pin "23") (pinfunction "UART_TX_23") (pintype "output"))
      (node (ref "IC8") (pin "81") (pinfunction "PB25_81") (pintype "bidirectional"))
      (node (ref "JP6") (pin "3") (pinfunction "3_3") (pintype "passive"))
    )
    (net (code "18") (name "CHARGER_NTC") (class "Default")
      (node (ref "J1") (pin "2") (pinfunction "S_2") (pintype "passive"))
      (node (ref "R8") (pin "1") (pinfunction "1_1") (pintype "passive"))
      (node (ref "R9") (pin "2") (pinfunction "2_2") (pintype "passive"))
    )
    (net (code "19") (name "CHARGER_STAT1") (class "Default")
      (node (ref "IC2") (pin "3") (pinfunction "STAT1_3") (pintype "bidirectional"))
      (node (ref "IC6") (pin "11") (pinfunction "I/OVCC3_11") (pintype "bidirectional"))
      (node (ref "R3") (pin "2") (pinfunction "2_2") (pintype "passive"))
    )
    (net (code "20") (name "CHARGER_STAT2") (class "Default")
      (node (ref "IC2") (pin "4") (pinfunction "STAT2_4") (pintype "bidirectional"))
      (node (ref "IC6") (pin "12") (pinfunction "I/OVCC2_12") (pintype "bidirectional"))
      (node (ref "R4") (pin "2") (pinfunction "2_2") (pintype "passive"))
    )
    (net (code "21") (name "CHARGER_VBAT_MEAS") (class "Default")
      (node (ref "C8") (pin "1") (pinfunction "1_1") (pintype "passive"))
      (node (ref "IC2") (pin "10") (pinfunction "VBAT_10") (pintype "bidirectional"))
      (node (ref "IC2") (pin "9") (pinfunction "VBAT_9") (pintype "bidirectional"))
      (node (ref "IC4") (pin "5") (pinfunction "CH2-_5") (pintype "bidirectional"))
      (node (ref "R14") (pin "2") (pinfunction "2_2") (pintype "passive"))
      (node (ref "T1") (pin "3") (pinfunction "D_3") (pintype "passive"))
    )
    (net (code "22") (name "CHARGER_VUSB_FIL") (class "Default")
      (node (ref "C1") (pin "1") (pinfunction "1_1") (pintype "passive"))
      (node (ref "C32") (pin "1") (pinfunction "1_1") (pintype "passive"))
      (node (ref "D1") (pin "2") (pinfunction "A_2") (pintype "passive"))
      (node (ref "D2") (pin "2") (pinfunction "A_2") (pintype "passive"))
      (node (ref "D3") (pin "2") (pinfunction "A_2") (pintype "passive"))
      (node (ref "D4") (pin "2") (pinfunction "A_2") (pintype "passive"))
      (node (ref "IC2") (pin "1") (pinfunction "VDD_1") (pintype "bidirectional"))
      (node (ref "IC2") (pin "2") (pinfunction "VDD_2") (pintype "bidirectional"))
      (node (ref "IC3") (pin "5") (pinfunction "VDD_5") (pintype "bidirectional"))
      (node (ref "IC6") (pin "10") (pinfunction "I/OVCC4_10") (pintype "bidirectional"))
      (node (ref "IC6") (pin "14") (pinfunction "VCC_14") (pintype "bidirectional"))
      (node (ref "IC6") (pin "8") (pinfunction "~{TS}_8") (pintype "bidirectional"))
      (node (ref "L2") (pin "1") (pinfunction "1_1") (pintype "passive"))
      (node (ref "R16") (pin "2") (pinfunction "2_2") (pintype "passive"))
      (node (ref "T1") (pin "1") (pinfunction "G_1") (pintype "passive"))
    )
    (net (code "23") (name "CHARGER_~{PG}") (class "Default")
      (node (ref "IC2") (pin "7") (pinfunction "~{PG}_7") (pintype "bidirectional"))
      (node (ref "IC6") (pin "13") (pinfunction "I/OVCC1_13") (pintype "bidirectional"))
      (node (ref "R5") (pin "2") (pinfunction "2_2") (pintype "passive"))
    )
    (net (code "24") (name "EXT_PWM_0") (class "Default")
      (node (ref "IC8") (pin "55") (pinfunction "PA19_55") (pintype "bidirectional"))
      (node (ref "J8") (pin "1") (pinfunction "S_1") (pintype "passive"))
    )
    (net (code "25") (name "EXT_PWM_1") (class "Default")
      (node (ref "IC8") (pin "54") (pinfunction "PA18_54") (pintype "bidirectional"))
      (node (ref "J8") (pin "2") (pinfunction "S_2") (pintype "passive"))
    )
    (net (code "26") (name "GND") (class "Default")
      (node (ref "C1") (pin "2") (pinfunction "2_2") (pintype "passive"))
      (node (ref "C10") (pin "2") (pinfunction "2_2") (pintype "passive"))
      (node (ref "C11") (pin "2") (pinfunction "2_2") (pintype "passive"))
      (node (ref "C12") (pin "2") (pinfunction "2_2") (pintype "passive"))
      (node (ref "C13") (pin "2") (pinfunction "2_2") (pintype "passive"))
      (node (ref "C14") (pin "2") (pinfunction "2_2") (pintype "passive"))
      (node (ref "C15") (pin "2") (pinfunction "2_2") (pintype "passive"))
      (node (ref "C16") (pin "2") (pinfunction "2_2") (pintype "passive"))
      (node (ref "C17") (pin "2") (pinfunction "2_2") (pintype "passive"))
      (node (ref "C18") (pin "2") (pinfunction "2_2") (pintype "passive"))
      (node (ref "C19") (pin "2") (pinfunction "2_2") (pintype "passive"))
      (node (ref "C2") (pin "2") (pinfunction "2_2") (pintype "passive"))
      (node (ref "C20") (pin "2") (pinfunction "2_2") (pintype "passive"))
      (node (ref "C21") (pin "2") (pinfunction "2_2") (pintype "passive"))
      (node (ref "C26") (pin "2") (pinfunction "2_2") (pintype "passive"))
      (node (ref "C27") (pin "2") (pinfunction "2_2") (pintype "passive"))
      (node (ref "C28") (pin "2") (pinfunction "2_2") (pintype "passive"))
      (node (ref "C29") (pin "2") (pinfunction "2_2") (pintype "passive"))
      (node (ref "C30") (pin "2") (pinfunction "2_2") (pintype "passive"))
      (node (ref "C31") (pin "2") (pinfunction "2_2") (pintype "passive"))
      (node (ref "C32") (pin "2") (pinfunction "2_2") (pintype "passive"))
      (node (ref "C33") (pin "2") (pinfunction "2_2") (pintype "passive"))
      (node (ref "C34") (pin "2") (pinfunction "2_2") (pintype "passive"))
      (node (ref "C35") (pin "2") (pinfunction "2_2") (pintype "passive"))
      (node (ref "C36") (pin "2") (pinfunction "2_2") (pintype "passive"))
      (node (ref "C37") (pin "2") (pinfunction "2_2") (pintype "passive"))
      (node (ref "C5") (pin "2") (pinfunction "2_2") (pintype "passive"))
      (node (ref "C6") (pin "2") (pinfunction "2_2") (pintype "passive"))
      (node (ref "C7") (pin "2") (pinfunction "2_2") (pintype "passive"))
      (node (ref "C8") (pin "2") (pinfunction "2_2") (pintype "passive"))
      (node (ref "IC1") (pin "7") (pinfunction "PGND_7") (pintype "bidirectional"))
      (node (ref "IC2") (pin "5") (pinfunction "VSS_5") (pintype "bidirectional"))
      (node (ref "IC3") (pin "2") (pinfunction "GND_2") (pintype "bidirectional"))
      (node (ref "IC4") (pin "10") (pinfunction "ADR1_10") (pintype "bidirectional"))
      (node (ref "IC4") (pin "2") (pinfunction "CH1-_2") (pintype "bidirectional"))
      (node (ref "IC4") (pin "3") (pinfunction "VSS_3") (pintype "bidirectional"))
      (node (ref "IC4") (pin "9") (pinfunction "ADR0_9") (pintype "bidirectional"))
      (node (ref "IC5") (pin "12") (pinfunction "GND_12") (pintype "power_in"))
      (node (ref "IC5") (pin "28") (pinfunction "GND_28") (pintype "power_in"))
      (node (ref "IC5") (pin "29") (pinfunction "GND_29") (pintype "power_in"))
      (node (ref "IC5") (pin "9") (pinfunction "GND_9") (pintype "power_in"))
      (node (ref "IC6") (pin "7") (pinfunction "GND_7") (pintype "bidirectional"))
      (node (ref "IC7") (pin "1") (pinfunction "GND_1") (pintype "power_in"))
      (node (ref "IC7") (pin "2") (pinfunction "GND_2") (pintype "power_in"))
      (node (ref "IC7") (pin "3") (pinfunction "GND_3") (pintype "power_in"))
      (node (ref "IC7") (pin "31") (pinfunction "GND_31") (pintype "power_in"))
      (node (ref "IC7") (pin "32") (pinfunction "GND_32") (pintype "power_in"))
      (node (ref "IC7") (pin "33") (pinfunction "GND_33") (pintype "power_in"))
      (node (ref "IC8") (pin "37") (pinfunction "GND_37") (pintype "power_in"))
      (node (ref "IC8") (pin "50") (pinfunction "GND_50") (pintype "power_in"))
      (node (ref "IC8") (pin "62") (pinfunction "GND_62") (pintype "power_in"))
      (node (ref "IC8") (pin "76") (pinfunction "GND_76") (pintype "power_in"))
      (node (ref "IC8") (pin "90") (pinfunction "GND_90") (pintype "power_in"))
      (node (ref "J1") (pin "3") (pinfunction "S_3") (pintype "passive"))
      (node (ref "J2") (pin "5") (pinfunction "GND_5") (pintype "power_in"))
      (node (ref "JP7") (pin "3") (pinfunction "3_3") (pintype "passive"))
      (node (ref "JP7") (pin "4") (pinfunction "4_4") (pintype "passive"))
      (node (ref "R10") (pin "1") (pinfunction "1_1") (pintype "passive"))
      (node (ref "R16") (pin "1") (pinfunction "1_1") (pintype "passive"))
      (node (ref "R17") (pin "1") (pinfunction "1_1") (pintype "passive"))
      (node (ref "R21") (pin "1") (pinfunction "1_1") (pintype "passive"))
      (node (ref "R22") (pin "1") (pinfunction "1_1") (pintype "passive"))
      (node (ref "R37") (pin "1") (pinfunction "1_1") (pintype "passive"))
      (node (ref "R43") (pin "1") (pinfunction "1_1") (pintype "passive"))
      (node (ref "R44") (pin "1") (pinfunction "1_1") (pintype "passive"))
      (node (ref "R45") (pin "1") (pinfunction "1_1") (pintype "passive"))
      (node (ref "R46") (pin "1") (pinfunction "1_1") (pintype "passive"))
      (node (ref "R47") (pin "1") (pinfunction "1_1") (pintype "passive"))
      (node (ref "R53") (pin "1") (pinfunction "1_1") (pintype "passive"))
      (node (ref "R54") (pin "1") (pinfunction "1_1") (pintype "passive"))
      (node (ref "R55") (pin "1") (pinfunction "1_1") (pintype "passive"))
      (node (ref "R56") (pin "1") (pinfunction "1_1") (pintype "passive"))
      (node (ref "R57") (pin "1") (pinfunction "1_1") (pintype "passive"))
      (node (ref "R7") (pin "1") (pinfunction "1_1") (pintype "passive"))
      (node (ref "R9") (pin "1") (pinfunction "1_1") (pintype "passive"))
      (node (ref "SV1") (pin "10") (pinfunction "10_10") (pintype "passive"))
      (node (ref "SV1") (pin "12") (pinfunction "12_12") (pintype "passive"))
      (node (ref "SV1") (pin "14") (pinfunction "14_14") (pintype "passive"))
      (node (ref "SV1") (pin "16") (pinfunction "16_16") (pintype "passive"))
      (node (ref "SV1") (pin "18") (pinfunction "18_18") (pintype "passive"))
      (node (ref "SV1") (pin "20") (pinfunction "20_20") (pintype "passive"))
      (node (ref "SV1") (pin "4") (pinfunction "4_4") (pintype "passive"))
      (node (ref "SV1") (pin "6") (pinfunction "6_6") (pintype "passive"))
      (node (ref "SV1") (pin "8") (pinfunction "8_8") (pintype "passive"))
      (node (ref "T12") (pin "2") (pinfunction "S_2") (pintype "passive"))
      (node (ref "X1") (pin "1") (pinfunction "P_1") (pintype "passive"))
      (node (ref "X1") (pin "3") (pinfunction "P_3") (pintype "passive"))
      (node (ref "X2") (pin "12") (pinfunction "6_12") (pintype "passive"))
      (node (ref "X2") (pin "6") (pinfunction "6_6") (pintype "passive"))
    )
    (net (code "27") (name "MISO_NC") (class "Default")
      (node (ref "IC8") (pin "49") (pinfunction "PA15_49") (pintype "bidirectional"))
      (node (ref "JP2") (pin "4") (pinfunction "4_4") (pintype "passive"))
    )
    (net (code "28") (name "Net-(C4-Pad2)") (class "Default")
      (node (ref "C4") (pin "2") (pinfunction "2_2") (pintype "passive"))
      (node (ref "R2") (pin "2") (pinfunction "2_2") (pintype "passive"))
    )
    (net (code "29") (name "Net-(C9-Pad1)") (class "Default")
      (node (ref "C9") (pin "1") (pinfunction "1_1") (pintype "passive"))
      (node (ref "J2") (pin "6") (pinfunction "SHIELD_6") (pintype "bidirectional"))
      (node (ref "J2") (pin "7") (pinfunction "SHIELD_7") (pintype "bidirectional"))
      (node (ref "J2") (pin "8") (pinfunction "SHIELD_8") (pintype "bidirectional"))
      (node (ref "J2") (pin "9") (pinfunction "SHIELD_9") (pintype "bidirectional"))
      (node (ref "R13") (pin "2") (pinfunction "2_2") (pintype "passive"))
    )
    (net (code "30") (name "Net-(D1-C)") (class "Default")
      (node (ref "D1") (pin "1") (pinfunction "C_1") (pintype "passive"))
      (node (ref "R3") (pin "1") (pinfunction "1_1") (pintype "passive"))
    )
    (net (code "31") (name "Net-(D2-C)") (class "Default")
      (node (ref "D2") (pin "1") (pinfunction "C_1") (pintype "passive"))
      (node (ref "R4") (pin "1") (pinfunction "1_1") (pintype "passive"))
    )
    (net (code "32") (name "Net-(D3-C)") (class "Default")
      (node (ref "D3") (pin "1") (pinfunction "C_1") (pintype "passive"))
      (node (ref "R5") (pin "1") (pinfunction "1_1") (pintype "passive"))
    )
    (net (code "33") (name "Net-(IC1-COMP)") (class "Default")
      (node (ref "IC1") (pin "4") (pinfunction "COMP_4") (pintype "bidirectional"))
      (node (ref "R2") (pin "1") (pinfunction "1_1") (pintype "passive"))
    )
    (net (code "34") (name "Net-(IC1-FB)") (class "Default")
      (node (ref "IC1") (pin "5") (pinfunction "FB_5") (pintype "bidirectional"))
      (node (ref "R12") (pin "1") (pinfunction "1_1") (pintype "passive"))
      (node (ref "R6") (pin "2") (pinfunction "2_2") (pintype "passive"))
    )
    (net (code "35") (name "Net-(IC1-LX)") (class "Default")
      (node (ref "IC1") (pin "8") (pinfunction "LX_8") (pintype "bidirectional"))
      (node (ref "L1") (pin "2") (pinfunction "2_2") (pintype "passive"))
    )
    (net (code "36") (name "Net-(IC1-VCC)") (class "Default")
      (node (ref "C3") (pin "1") (pinfunction "1_1") (pintype "passive"))
      (node (ref "IC1") (pin "2") (pinfunction "VCC_2") (pintype "bidirectional"))
      (node (ref "R1") (pin "1") (pinfunction "1_1") (pintype "passive"))
    )
    (net (code "37") (name "Net-(IC2-PROG)") (class "Default")
      (node (ref "IC2") (pin "6") (pinfunction "PROG_6") (pintype "bidirectional"))
      (node (ref "R7") (pin "2") (pinfunction "2_2") (pintype "passive"))
    )
    (net (code "38") (name "Net-(IC2-THERM)") (class "Default")
      (node (ref "IC2") (pin "8") (pinfunction "THERM_8") (pintype "bidirectional"))
      (node (ref "R8") (pin "2") (pinfunction "2_2") (pintype "passive"))
    )
    (net (code "39") (name "Net-(IC3-D+)") (class "Default")
      (node (ref "IC3") (pin "4") (pinfunction "D+_4") (pintype "bidirectional"))
      (node (ref "J2") (pin "3") (pinfunction "D+_3") (pintype "bidirectional"))
      (node (ref "L3") (pin "1") (pinfunction "1_1") (pintype "passive"))
    )
    (net (code "40") (name "Net-(IC3-D-)") (class "Default")
      (node (ref "IC3") (pin "3") (pinfunction "D-_3") (pintype "bidirectional"))
      (node (ref "J2") (pin "2") (pinfunction "D-_2") (pintype "bidirectional"))
      (node (ref "L3") (pin "4") (pinfunction "4_4") (pintype "passive"))
    )
    (net (code "41") (name "Net-(IC4-CH1+)") (class "Default")
      (node (ref "IC4") (pin "1") (pinfunction "CH1+_1") (pintype "bidirectional"))
      (node (ref "R15") (pin "2") (pinfunction "2_2") (pintype "passive"))
      (node (ref "R17") (pin "2") (pinfunction "2_2") (pintype "passive"))
    )
    (net (code "42") (name "Net-(IC5-1P3V_TP)") (class "Default")
      (node (ref "C26") (pin "1") (pinfunction "1_1") (pintype "passive"))
      (node (ref "C28") (pin "1") (pinfunction "1_1") (pintype "passive"))
      (node (ref "C31") (pin "1") (pinfunction "1_1") (pintype "passive"))
      (node (ref "IC5") (pin "24") (pinfunction "1P3V_TP_24") (pintype "bidirectional"))
    )
    (net (code "43") (name "Net-(IC5-CHIP_EN)") (class "Default")
      (node (ref "IC5") (pin "22") (pinfunction "CHIP_EN_22") (pintype "bidirectional"))
      (node (ref "R22") (pin "2") (pinfunction "2_2") (pintype "passive"))
      (node (ref "R32") (pin "2") (pinfunction "2_2") (pintype "passive"))
    )
    (net (code "44") (name "Net-(IC5-IRQN)") (class "Default")
      (node (ref "IC5") (pin "13") (pinfunction "IRQN_13") (pintype "bidirectional"))
      (node (ref "R25") (pin "2") (pinfunction "2_2") (pintype "passive"))
    )
    (net (code "45") (name "Net-(IC5-RESETN)") (class "Default")
      (node (ref "IC5") (pin "4") (pinfunction "RESETN_4") (pintype "bidirectional"))
      (node (ref "R21") (pin "2") (pinfunction "2_2") (pintype "passive"))
      (node (ref "R33") (pin "2") (pinfunction "2_2") (pintype "passive"))
    )
    (net (code "46") (name "Net-(IC5-SPI_CFG)") (class "Default")
      (node (ref "IC5") (pin "10") (pinfunction "SPI_CFG_10") (pintype "bidirectional"))
      (node (ref "R34") (pin "1") (pinfunction "1_1") (pintype "passive"))
    )
    (net (code "47") (name "Net-(IC5-SPI_MISO)") (class "Default")
      (node (ref "IC5") (pin "17") (pinfunction "SPI_MISO_17") (pintype "bidirectional"))
      (node (ref "R29") (pin "2") (pinfunction "2_2") (pintype "passive"))
    )
    (net (code "48") (name "Net-(IC5-SPI_MOSI)") (class "Default")
      (node (ref "IC5") (pin "15") (pinfunction "SPI_MOSI_15") (pintype "bidirectional"))
      (node (ref "R27") (pin "2") (pinfunction "2_2") (pintype "passive"))
    )
    (net (code "49") (name "Net-(IC5-SPI_SCK)") (class "Default")
      (node (ref "IC5") (pin "18") (pinfunction "SPI_SCK_18") (pintype "bidirectional"))
      (node (ref "R30") (pin "2") (pinfunction "2_2") (pintype "passive"))
    )
    (net (code "50") (name "Net-(IC5-SPI_SSN)") (class "Default")
      (node (ref "IC5") (pin "16") (pinfunction "SPI_SSN_16") (pintype "bidirectional"))
      (node (ref "R28") (pin "2") (pinfunction "2_2") (pintype "passive"))
    )
    (net (code "51") (name "Net-(IC5-UART_RXD)") (class "Default")
      (node (ref "IC5") (pin "19") (pinfunction "UART_RXD_19") (pintype "bidirectional"))
      (node (ref "R31") (pin "2") (pinfunction "2_2") (pintype "passive"))
    )
    (net (code "52") (name "Net-(IC5-UART_TXD)") (class "Default")
      (node (ref "IC5") (pin "14") (pinfunction "UART_TXD_14") (pintype "bidirectional"))
      (node (ref "R26") (pin "2") (pinfunction "2_2") (pintype "passive"))
    )
    (net (code "53") (name "Net-(IC5-WAKE)") (class "Default")
      (node (ref "IC5") (pin "11") (pinfunction "WAKE_11") (pintype "bidirectional"))
      (node (ref "R24") (pin "2") (pinfunction "2_2") (pintype "passive"))
    )
    (net (code "54") (name "Net-(IC7-~{RST})") (class "Default")
      (node (ref "C37") (pin "1") (pinfunction "1_1") (pintype "passive"))
      (node (ref "IC7") (pin "21") (pinfunction "~{RST}_21") (pintype "input"))
      (node (ref "R36") (pin "1") (pinfunction "1_1") (pintype "passive"))
    )
    (net (code "55") (name "Net-(J2-VCC)") (class "Default")
      (node (ref "J2") (pin "1") (pinfunction "VCC_1") (pintype "bidirectional"))
      (node (ref "L2") (pin "2") (pinfunction "2_2") (pintype "passive"))
    )
    (net (code "56") (name "Net-(R11-Pad1)") (class "Default")
      (node (ref "R11") (pin "1") (pinfunction "1_1") (pintype "passive"))
      (node (ref "R12") (pin "2") (pinfunction "2_2") (pintype "passive"))
    )
    (net (code "57") (name "Net-(R20-Pad1)") (class "Default")
      (node (ref "R20") (pin "1") (pinfunction "1_1") (pintype "passive"))
      (node (ref "X1") (pin "2") (pinfunction "S_2") (pintype "passive"))
      (node (ref "X1") (pin "4") (pinfunction "S_4") (pintype "passive"))
    )
    (net (code "58") (name "Net-(T2-D)") (class "Default")
      (node (ref "R38") (pin "2") (pinfunction "2_2") (pintype "passive"))
      (node (ref "T2") (pin "3") (pinfunction "D_3") (pintype "passive"))
    )
    (net (code "59") (name "Net-(T3-D)") (class "Default")
      (node (ref "R39") (pin "2") (pinfunction "2_2") (pintype "passive"))
      (node (ref "T3") (pin "3") (pinfunction "D_3") (pintype "passive"))
    )
    (net (code "60") (name "Net-(T4-D)") (class "Default")
      (node (ref "R40") (pin "2") (pinfunction "2_2") (pintype "passive"))
      (node (ref "T4") (pin "3") (pinfunction "D_3") (pintype "passive"))
    )
    (net (code "61") (name "Net-(T5-D)") (class "Default")
      (node (ref "R41") (pin "2") (pinfunction "2_2") (pintype "passive"))
      (node (ref "T5") (pin "3") (pinfunction "D_3") (pintype "passive"))
    )
    (net (code "62") (name "Net-(T6-D)") (class "Default")
      (node (ref "R42") (pin "2") (pinfunction "2_2") (pintype "passive"))
      (node (ref "T6") (pin "3") (pinfunction "D_3") (pintype "passive"))
    )
    (net (code "63") (name "Net-(T7-D)") (class "Default")
      (node (ref "R48") (pin "2") (pinfunction "2_2") (pintype "passive"))
      (node (ref "T7") (pin "3") (pinfunction "D_3") (pintype "passive"))
    )
    (net (code "64") (name "Net-(T8-D)") (class "Default")
      (node (ref "R49") (pin "2") (pinfunction "2_2") (pintype "passive"))
      (node (ref "T8") (pin "3") (pinfunction "D_3") (pintype "passive"))
    )
    (net (code "65") (name "Net-(T9-D)") (class "Default")
      (node (ref "R50") (pin "2") (pinfunction "2_2") (pintype "passive"))
      (node (ref "T9") (pin "3") (pinfunction "D_3") (pintype "passive"))
    )
    (net (code "66") (name "Net-(T10-D)") (class "Default")
      (node (ref "R51") (pin "2") (pinfunction "2_2") (pintype "passive"))
      (node (ref "T10") (pin "3") (pinfunction "D_3") (pintype "passive"))
    )
    (net (code "67") (name "Net-(T11-D)") (class "Default")
      (node (ref "R52") (pin "2") (pinfunction "2_2") (pintype "passive"))
      (node (ref "T11") (pin "3") (pinfunction "D_3") (pintype "passive"))
    )
    (net (code "68") (name "Net-(T12-D)") (class "Default")
      (node (ref "T12") (pin "3") (pinfunction "D_3") (pintype "passive"))
      (node (ref "X3") (pin "1") (pinfunction "1_1") (pintype "passive"))
      (node (ref "X3") (pin "10") (pinfunction "10_10") (pintype "passive"))
      (node (ref "X3") (pin "11") (pinfunction "11_11") (pintype "passive"))
      (node (ref "X3") (pin "12") (pinfunction "12_12") (pintype "passive"))
      (node (ref "X3") (pin "13") (pinfunction "13_13") (pintype "passive"))
      (node (ref "X3") (pin "14") (pinfunction "14_14") (pintype "passive"))
      (node (ref "X3") (pin "19") (pinfunction "19_19") (pintype "passive"))
      (node (ref "X3") (pin "20") (pinfunction "20_20") (pintype "passive"))
      (node (ref "X3") (pin "5") (pinfunction "5_5") (pintype "passive"))
      (node (ref "X3") (pin "6") (pinfunction "6_6") (pintype "passive"))
    )
    (net (code "69") (name "OLED_D{slash}C") (class "Default")
      (node (ref "IC8") (pin "44") (pinfunction "PC14_44") (pintype "bidirectional"))
      (node (ref "X3") (pin "4") (pinfunction "4_4") (pintype "passive"))
    )
    (net (code "70") (name "OLED_EN") (class "Default")
      (node (ref "IC8") (pin "43") (pinfunction "PB15_43") (pintype "bidirectional"))
      (node (ref "R57") (pin "2") (pinfunction "2_2") (pintype "passive"))
      (node (ref "T12") (pin "1") (pinfunction "G_1") (pintype "passive"))
    )
    (net (code "71") (name "OLED_SPI_MOSI") (class "Default")
      (node (ref "IC8") (pin "46") (pinfunction "PA12_46") (pintype "bidirectional"))
      (node (ref "JP2") (pin "1") (pinfunction "1_1") (pintype "passive"))
      (node (ref "X3") (pin "8") (pinfunction "8_8") (pintype "passive"))
    )
    (net (code "72") (name "OLED_SPI_SCLK") (class "Default")
      (node (ref "IC8") (pin "47") (pinfunction "PA13_47") (pintype "bidirectional"))
      (node (ref "JP2") (pin "2") (pinfunction "2_2") (pintype "passive"))
      (node (ref "X3") (pin "7") (pinfunction "7_7") (pintype "passive"))
    )
    (net (code "73") (name "RES0") (class "Default")
      (node (ref "IC8") (pin "41") (pinfunction "PB13_41") (pintype "bidirectional"))
      (node (ref "JP5") (pin "1") (pinfunction "1_1") (pintype "passive"))
    )
    (net (code "74") (name "RES1") (class "Default")
      (node (ref "IC8") (pin "40") (pinfunction "PB12_40") (pintype "bidirectional"))
      (node (ref "JP5") (pin "2") (pinfunction "2_2") (pintype "passive"))
    )
    (net (code "75") (name "RES2") (class "Default")
      (node (ref "IC8") (pin "39") (pinfunction "PB11_39") (pintype "bidirectional"))
      (node (ref "JP5") (pin "3") (pinfunction "3_3") (pintype "passive"))
    )
    (net (code "76") (name "SENSOR_EN_0") (class "Default")
      (node (ref "IC8") (pin "17") (pinfunction "PA4_17") (pintype "bidirectional"))
      (node (ref "R37") (pin "2") (pinfunction "2_2") (pintype "passive"))
      (node (ref "T2") (pin "1") (pinfunction "G_1") (pintype "passive"))
    )
    (net (code "77") (name "SENSOR_EN_1") (class "Default")
      (node (ref "IC8") (pin "18") (pinfunction "PA5_18") (pintype "bidirectional"))
      (node (ref "R43") (pin "2") (pinfunction "2_2") (pintype "passive"))
      (node (ref "T3") (pin "1") (pinfunction "G_1") (pintype "passive"))
    )
    (net (code "78") (name "SENSOR_EN_2") (class "Default")
      (node (ref "IC8") (pin "19") (pinfunction "PA6_19") (pintype "bidirectional"))
      (node (ref "R44") (pin "2") (pinfunction "2_2") (pintype "passive"))
      (node (ref "T4") (pin "1") (pinfunction "G_1") (pintype "passive"))
    )
    (net (code "79") (name "SENSOR_EN_3") (class "Default")
      (node (ref "IC8") (pin "20") (pinfunction "PA7_20") (pintype "bidirectional"))
      (node (ref "R45") (pin "2") (pinfunction "2_2") (pintype "passive"))
      (node (ref "T5") (pin "1") (pinfunction "G_1") (pintype "passive"))
    )
    (net (code "80") (name "SENSOR_EN_4") (class "Default")
      (node (ref "IC8") (pin "21") (pinfunction "PC5_21") (pintype "bidirectional"))
      (node (ref "R46") (pin "2") (pinfunction "2_2") (pintype "passive"))
      (node (ref "T6") (pin "1") (pinfunction "G_1") (pintype "passive"))
    )
    (net (code "81") (name "SENSOR_EN_5") (class "Default")
      (node (ref "IC8") (pin "22") (pinfunction "PC6_22") (pintype "bidirectional"))
      (node (ref "R47") (pin "2") (pinfunction "2_2") (pintype "passive"))
      (node (ref "T7") (pin "1") (pinfunction "G_1") (pintype "passive"))
    )
    (net (code "82") (name "SENSOR_EN_6") (class "Default")
      (node (ref "IC8") (pin "23") (pinfunction "PC7_23") (pintype "bidirectional"))
      (node (ref "R53") (pin "2") (pinfunction "2_2") (pintype "passive"))
      (node (ref "T8") (pin "1") (pinfunction "G_1") (pintype "passive"))
    )
    (net (code "83") (name "SENSOR_EN_7") (class "Default")
      (node (ref "IC8") (pin "27") (pinfunction "PA9_27") (pintype "bidirectional"))
      (node (ref "R54") (pin "2") (pinfunction "2_2") (pintype "passive"))
      (node (ref "T9") (pin "1") (pinfunction "G_1") (pintype "passive"))
    )
    (net (code "84") (name "SENSOR_EN_8") (class "Default")
      (node (ref "IC8") (pin "28") (pinfunction "PA10_28") (pintype "bidirectional"))
      (node (ref "R55") (pin "2") (pinfunction "2_2") (pintype "passive"))
      (node (ref "T10") (pin "1") (pinfunction "G_1") (pintype "passive"))
    )
    (net (code "85") (name "SENSOR_EN_9") (class "Default")
      (node (ref "IC8") (pin "29") (pinfunction "PA11_29") (pintype "bidirectional"))
      (node (ref "R56") (pin "2") (pinfunction "2_2") (pintype "passive"))
      (node (ref "T11") (pin "1") (pinfunction "G_1") (pintype "passive"))
    )
    (net (code "86") (name "SENSOR_INT_0") (class "Default")
      (node (ref "IC8") (pin "30") (pinfunction "PC8_30") (pintype "bidirectional"))
      (node (ref "J3") (pin "3") (pinfunction "3_3") (pintype "passive"))
    )
    (net (code "87") (name "SENSOR_INT_1") (class "Default")
      (node (ref "IC8") (pin "31") (pinfunction "PC9_31") (pintype "bidirectional"))
      (node (ref "J4") (pin "3") (pinfunction "3_3") (pintype "passive"))
    )
    (net (code "88") (name "SENSOR_INT_2") (class "Default")
      (node (ref "IC8") (pin "32") (pinfunction "PC10_32") (pintype "bidirectional"))
      (node (ref "J5") (pin "3") (pinfunction "3_3") (pintype "passive"))
    )
    (net (code "89") (name "SENSOR_INT_3") (class "Default")
      (node (ref "IC8") (pin "33") (pinfunction "PC11_33") (pintype "bidirectional"))
      (node (ref "J6") (pin "3") (pinfunction "3_3") (pintype "passive"))
    )
    (net (code "90") (name "SENSOR_INT_4") (class "Default")
      (node (ref "IC8") (pin "34") (pinfunction "PC12_34") (pintype "bidirectional"))
      (node (ref "J7") (pin "3") (pinfunction "3_3") (pintype "passive"))
    )
    (net (code "91") (name "SENSOR_INT_5") (class "Default")
      (node (ref "IC8") (pin "35") (pinfunction "PC13_35") (pintype "bidirectional"))
      (node (ref "J9") (pin "3") (pinfunction "3_3") (pintype "passive"))
    )
    (net (code "92") (name "SENSOR_INT_6") (class "Default")
      (node (ref "IC8") (pin "13") (pinfunction "PB6_13") (pintype "bidirectional"))
      (node (ref "J10") (pin "3") (pinfunction "3_3") (pintype "passive"))
    )
    (net (code "93") (name "SENSOR_INT_7") (class "Default")
      (node (ref "IC8") (pin "14") (pinfunction "PB7_14") (pintype "bidirectional"))
      (node (ref "J11") (pin "3") (pinfunction "3_3") (pintype "passive"))
    )
    (net (code "94") (name "SENSOR_INT_8") (class "Default")
      (node (ref "IC8") (pin "15") (pinfunction "PB8_15") (pintype "bidirectional"))
      (node (ref "J12") (pin "3") (pinfunction "3_3") (pintype "passive"))
    )
    (net (code "95") (name "SENSOR_INT_9") (class "Default")
      (node (ref "IC8") (pin "16") (pinfunction "PB9_16") (pintype "bidirectional"))
      (node (ref "J13") (pin "3") (pinfunction "3_3") (pintype "passive"))
    )
    (net (code "96") (name "SENSOR_IN_0") (class "Default")
      (node (ref "IC8") (pin "99") (pinfunction "PB2_99") (pintype "bidirectional"))
      (node (ref "J3") (pin "1") (pinfunction "1_1") (pintype "passive"))
      (node (ref "R38") (pin "1") (pinfunction "1_1") (pintype "passive"))
    )
    (net (code "97") (name "SENSOR_IN_1") (class "Default")
      (node (ref "IC8") (pin "100") (pinfunction "PB3_100") (pintype "bidirectional"))
      (node (ref "J4") (pin "1") (pinfunction "1_1") (pintype "passive"))
      (node (ref "R39") (pin "1") (pinfunction "1_1") (pintype "passive"))
    )
    (net (code "98") (name "SENSOR_IN_2") (class "Default")
      (node (ref "IC8") (pin "3") (pinfunction "PC0_3") (pintype "bidirectional"))
      (node (ref "J5") (pin "1") (pinfunction "1_1") (pintype "passive"))
      (node (ref "R40") (pin "1") (pinfunction "1_1") (pintype "passive"))
    )
    (net (code "99") (name "SENSOR_IN_3") (class "Default")
      (node (ref "IC8") (pin "4") (pinfunction "PC1_4") (pintype "bidirectional"))
      (node (ref "J6") (pin "1") (pinfunction "1_1") (pintype "passive"))
      (node (ref "R41") (pin "1") (pinfunction "1_1") (pintype "passive"))
    )
    (net (code "100") (name "SENSOR_IN_4") (class "Default")
      (node (ref "IC8") (pin "5") (pinfunction "PC2_5") (pintype "bidirectional"))
      (node (ref "J7") (pin "1") (pinfunction "1_1") (pintype "passive"))
      (node (ref "R42") (pin "1") (pinfunction "1_1") (pintype "passive"))
    )
    (net (code "101") (name "SENSOR_IN_5") (class "Default")
      (node (ref "IC8") (pin "6") (pinfunction "PC3_6") (pintype "bidirectional"))
      (node (ref "J9") (pin "1") (pinfunction "1_1") (pintype "passive"))
      (node (ref "R48") (pin "1") (pinfunction "1_1") (pintype "passive"))
    )
    (net (code "102") (name "SENSOR_IN_6") (class "Default")
      (node (ref "IC8") (pin "7") (pinfunction "PA2_7") (pintype "bidirectional"))
      (node (ref "J10") (pin "1") (pinfunction "1_1") (pintype "passive"))
      (node (ref "R49") (pin "1") (pinfunction "1_1") (pintype "passive"))
    )
    (net (code "103") (name "SENSOR_IN_7") (class "Default")
      (node (ref "IC8") (pin "8") (pinfunction "PA3_8") (pintype "bidirectional"))
      (node (ref "J11") (pin "1") (pinfunction "1_1") (pintype "passive"))
      (node (ref "R50") (pin "1") (pinfunction "1_1") (pintype "passive"))
    )
    (net (code "104") (name "SENSOR_IN_8") (class "Default")
      (node (ref "IC8") (pin "9") (pinfunction "PB4_9") (pintype "bidirectional"))
      (node (ref "J12") (pin "1") (pinfunction "1_1") (pintype "passive"))
      (node (ref "R51") (pin "1") (pinfunction "1_1") (pintype "passive"))
    )
    (net (code "105") (name "SENSOR_IN_9") (class "Default")
      (node (ref "IC8") (pin "10") (pinfunction "PB5_10") (pintype "bidirectional"))
      (node (ref "J13") (pin "1") (pinfunction "1_1") (pintype "passive"))
      (node (ref "R52") (pin "1") (pinfunction "1_1") (pintype "passive"))
    )
    (net (code "106") (name "STAT1_TRANS") (class "Default")
      (node (ref "IC6") (pin "4") (pinfunction "I/OVL3_4") (pintype "bidirectional"))
      (node (ref "IC8") (pin "65") (pinfunction "PB17_65") (pintype "bidirectional"))
    )
    (net (code "107") (name "STAT2_TRANS") (class "Default")
      (node (ref "IC6") (pin "3") (pinfunction "I/OVL2_3") (pintype "bidirectional"))
      (node (ref "IC8") (pin "64") (pinfunction "PB16_64") (pintype "bidirectional"))
    )
    (net (code "108") (name "SWDCLK") (class "Default")
      (node (ref "IC8") (pin "93") (pinfunction "PA30_93") (pintype "bidirectional"))
      (node (ref "SV1") (pin "9") (pinfunction "9_9") (pintype "passive"))
    )
    (net (code "109") (name "SWDIO") (class "Default")
      (node (ref "IC8") (pin "94") (pinfunction "PA31_94") (pintype "bidirectional"))
      (node (ref "SV1") (pin "7") (pinfunction "7_7") (pintype "passive"))
    )
    (net (code "110") (name "UI_BUTTON_INT_0") (class "Default")
      (node (ref "IC8") (pin "61") (pinfunction "PC21_61") (pintype "bidirectional"))
      (node (ref "X2") (pin "2") (pinfunction "2_2") (pintype "passive"))
      (node (ref "X2") (pin "8") (pinfunction "2_8") (pintype "passive"))
    )
    (net (code "111") (name "UI_BUTTON_INT_1") (class "Default")
      (node (ref "IC8") (pin "60") (pinfunction "PC20_60") (pintype "bidirectional"))
      (node (ref "X2") (pin "3") (pinfunction "3_3") (pintype "passive"))
      (node (ref "X2") (pin "9") (pinfunction "3_9") (pintype "passive"))
    )
    (net (code "112") (name "UI_BUTTON_INT_2") (class "Default")
      (node (ref "IC8") (pin "59") (pinfunction "PC19_59") (pintype "bidirectional"))
      (node (ref "X2") (pin "10") (pinfunction "4_10") (pintype "passive"))
      (node (ref "X2") (pin "4") (pinfunction "4_4") (pintype "passive"))
    )
    (net (code "113") (name "UI_BUTTON_INT_3") (class "Default")
      (node (ref "IC8") (pin "58") (pinfunction "PC18_58") (pintype "bidirectional"))
      (node (ref "X2") (pin "11") (pinfunction "5_11") (pintype "passive"))
      (node (ref "X2") (pin "5") (pinfunction "5_5") (pintype "passive"))
    )
    (net (code "114") (name "USB_CON_INT_TRANS") (class "Default")
      (node (ref "IC6") (pin "5") (pinfunction "I/OVL4_5") (pintype "bidirectional"))
      (node (ref "IC8") (pin "42") (pinfunction "PB14_42") (pintype "bidirectional"))
    )
    (net (code "115") (name "USB_D_FIL_N") (class "Default")
      (node (ref "IC8") (pin "74") (pinfunction "PA24_74") (pintype "bidirectional"))
      (node (ref "L3") (pin "3") (pinfunction "3_3") (pintype "passive"))
    )
    (net (code "116") (name "USB_D_FIL_P") (class "Default")
      (node (ref "IC8") (pin "75") (pinfunction "PA25_75") (pintype "bidirectional"))
      (node (ref "L3") (pin "2") (pinfunction "2_2") (pintype "passive"))
    )
    (net (code "117") (name "V+") (class "Default")
      (node (ref "C2") (pin "1") (pinfunction "1_1") (pintype "passive"))
      (node (ref "D4") (pin "1") (pinfunction "C_1") (pintype "passive"))
      (node (ref "IC1") (pin "1") (pinfunction "VIN_1") (pintype "bidirectional"))
      (node (ref "IC1") (pin "3") (pinfunction "~{SHDN}_3") (pintype "bidirectional"))
      (node (ref "R1") (pin "2") (pinfunction "2_2") (pintype "passive"))
      (node (ref "T1") (pin "2") (pinfunction "S_2") (pintype "passive"))
    )
    (net (code "118") (name "VBAT") (class "Default")
      (node (ref "IC4") (pin "4") (pinfunction "CH2+_4") (pintype "bidirectional"))
      (node (ref "J1") (pin "1") (pinfunction "S_1") (pintype "passive"))
      (node (ref "R14") (pin "1") (pinfunction "1_1") (pintype "passive"))
      (node (ref "R15") (pin "1") (pinfunction "1_1") (pintype "passive"))
    )
    (net (code "119") (name "VDDCORE") (class "Default")
      (node (ref "C25") (pin "1") (pinfunction "1_1") (pintype "passive"))
      (node (ref "C29") (pin "1") (pinfunction "1_1") (pintype "passive"))
      (node (ref "IC8") (pin "89") (pinfunction "VDDCORE_89") (pintype "bidirectional"))
      (node (ref "L5") (pin "2") (pinfunction "2_2") (pintype "passive"))
    )
    (net (code "120") (name "VDDOUT") (class "Default")
      (node (ref "IC8") (pin "91") (pinfunction "VDDOUT_91") (pintype "bidirectional"))
      (node (ref "L5") (pin "1") (pinfunction "1_1") (pintype "passive"))
    )
    (net (code "121") (name "VIN") (class "Default")
      (node (ref "JP7") (pin "2") (pinfunction "2_2") (pintype "passive"))
    )
    (net (code "122") (name "WIFI_CHIP_EN") (class "Default")
      (node (ref "IC8") (pin "87") (pinfunction "PA27_87") (pintype "bidirectional"))
      (node (ref "R32") (pin "1") (pinfunction "1_1") (pintype "passive"))
    )
    (net (code "123") (name "WIFI_IRQN") (class "Default")
      (node (ref "IC8") (pin "57") (pinfunction "PC17_57") (pintype "bidirectional"))
      (node (ref "R25") (pin "1") (pinfunction "1_1") (pintype "passive"))
    )
    (net (code "124") (name "WIFI_RESETN") (class "Default")
      (node (ref "IC8") (pin "84") (pinfunction "PC26_84") (pintype "bidirectional"))
      (node (ref "R33") (pin "1") (pinfunction "1_1") (pintype "passive"))
    )
    (net (code "125") (name "WIFI_SPI_MISO") (class "Default")
      (node (ref "IC8") (pin "97") (pinfunction "PB0_97") (pintype "bidirectional"))
      (node (ref "JP1") (pin "2") (pinfunction "2_2") (pintype "passive"))
      (node (ref "R29") (pin "1") (pinfunction "1_1") (pintype "passive"))
    )
    (net (code "126") (name "WIFI_SPI_MOSI") (class "Default")
      (node (ref "IC8") (pin "95") (pinfunction "PB30_95") (pintype "bidirectional"))
      (node (ref "JP1") (pin "4") (pinfunction "4_4") (pintype "passive"))
      (node (ref "R27") (pin "1") (pinfunction "1_1") (pintype "passive"))
    )
    (net (code "127") (name "WIFI_SPI_SCK") (class "Default")
      (node (ref "IC8") (pin "98") (pinfunction "PB1_98") (pintype "bidirectional"))
      (node (ref "JP1") (pin "1") (pinfunction "1_1") (pintype "passive"))
      (node (ref "R30") (pin "1") (pinfunction "1_1") (pintype "passive"))
    )
    (net (code "128") (name "WIFI_SPI_SSN") (class "Default")
      (node (ref "IC8") (pin "96") (pinfunction "PB31_96") (pintype "bidirectional"))
      (node (ref "JP1") (pin "3") (pinfunction "3_3") (pintype "passive"))
      (node (ref "R28") (pin "1") (pinfunction "1_1") (pintype "passive"))
    )
    (net (code "129") (name "WIFI_UART1_RXD") (class "Default")
      (node (ref "IC8") (pin "85") (pinfunction "PC27_85") (pintype "bidirectional"))
      (node (ref "JP4") (pin "2") (pinfunction "2_2") (pintype "passive"))
      (node (ref "R31") (pin "1") (pinfunction "1_1") (pintype "passive"))
    )
    (net (code "130") (name "WIFI_UART1_TXD") (class "Default")
      (node (ref "IC8") (pin "86") (pinfunction "PC28_86") (pintype "bidirectional"))
      (node (ref "JP4") (pin "1") (pinfunction "1_1") (pintype "passive"))
      (node (ref "R26") (pin "1") (pinfunction "1_1") (pintype "passive"))
    )
    (net (code "131") (name "WIFI_WAKE") (class "Default")
      (node (ref "IC8") (pin "56") (pinfunction "PC16_56") (pintype "bidirectional"))
      (node (ref "R24") (pin "1") (pinfunction "1_1") (pintype "passive"))
    )
    (net (code "132") (name "XIN32") (class "Default")
      (node (ref "C35") (pin "1") (pinfunction "1_1") (pintype "passive"))
      (node (ref "IC8") (pin "1") (pinfunction "PA0_1") (pintype "bidirectional"))
      (node (ref "Q1") (pin "1") (pinfunction "1_1") (pintype "passive"))
    )
    (net (code "133") (name "XOUT32") (class "Default")
      (node (ref "C36") (pin "1") (pinfunction "1_1") (pintype "passive"))
      (node (ref "IC8") (pin "2") (pinfunction "PA1_2") (pintype "bidirectional"))
      (node (ref "Q1") (pin "2") (pinfunction "2_2") (pintype "passive"))
    )
    (net (code "134") (name "unconnected-(IC3-P$1-Pad1)") (class "Default")
      (node (ref "IC3") (pin "1") (pinfunction "P$1_1") (pintype "no_connect"))
    )
    (net (code "135") (name "unconnected-(IC5-GPIO_1-Pad21)") (class "Default")
      (node (ref "IC5") (pin "21") (pinfunction "GPIO_1_21") (pintype "bidirectional"))
    )
    (net (code "136") (name "unconnected-(IC5-GPIO_3-Pad25)") (class "Default")
      (node (ref "IC5") (pin "25") (pinfunction "GPIO_3_25") (pintype "bidirectional"))
    )
    (net (code "137") (name "unconnected-(IC5-GPIO_4-Pad26)") (class "Default")
      (node (ref "IC5") (pin "26") (pinfunction "GPIO_4_26") (pintype "bidirectional"))
    )
    (net (code "138") (name "unconnected-(IC5-GPIO_5-Pad27)") (class "Default")
      (node (ref "IC5") (pin "27") (pinfunction "GPIO_5_27") (pintype "bidirectional"))
    )
    (net (code "139") (name "unconnected-(IC5-GPIO_6-Pad1)") (class "Default")
      (node (ref "IC5") (pin "1") (pinfunction "GPIO_6_1") (pintype "bidirectional"))
    )
    (net (code "140") (name "unconnected-(IC5-I2C_SCL-Pad2)") (class "Default")
      (node (ref "IC5") (pin "2") (pinfunction "I2C_SCL_2") (pintype "bidirectional"))
    )
    (net (code "141") (name "unconnected-(IC5-I2C_SDA-Pad3)") (class "Default")
      (node (ref "IC5") (pin "3") (pinfunction "I2C_SDA_3") (pintype "bidirectional"))
    )
    (net (code "142") (name "unconnected-(IC5-NC-Pad5)") (class "Default")
      (node (ref "IC5") (pin "5") (pinfunction "NC_5") (pintype "no_connect"))
    )
    (net (code "143") (name "unconnected-(IC5-NC-Pad6)") (class "Default")
      (node (ref "IC5") (pin "6") (pinfunction "NC_6") (pintype "no_connect"))
    )
    (net (code "144") (name "unconnected-(IC5-NC-Pad7)") (class "Default")
      (node (ref "IC5") (pin "7") (pinfunction "NC_7") (pintype "no_connect"))
    )
    (net (code "145") (name "unconnected-(IC5-NC-Pad8)") (class "Default")
      (node (ref "IC5") (pin "8") (pinfunction "NC_8") (pintype "no_connect"))
    )
    (net (code "146") (name "unconnected-(IC6-NC-Pad6)") (class "Default")
      (node (ref "IC6") (pin "6") (pinfunction "NC_6") (pintype "no_connect"))
    )
    (net (code "147") (name "unconnected-(IC6-NC-Pad9)") (class "Default")
      (node (ref "IC6") (pin "9") (pinfunction "NC_9") (pintype "no_connect"))
    )
    (net (code "148") (name "unconnected-(IC7-BK_O-Pad10)") (class "Default")
      (node (ref "IC7") (pin "10") (pinfunction "BK_O_10") (pintype "output"))
    )
    (net (code "149") (name "unconnected-(IC7-NC-Pad20)") (class "Default")
      (node (ref "IC7") (pin "20") (pinfunction "NC_20") (pintype "no_connect"))
    )
    (net (code "150") (name "unconnected-(IC7-P0_2-Pad30)") (class "Default")
      (node (ref "IC7") (pin "30") (pinfunction "P0_2_30") (pintype "output"))
    )
    (net (code "151") (name "unconnected-(IC7-P0_7-Pad29)") (class "Default")
      (node (ref "IC7") (pin "29") (pinfunction "P0_7_29") (pintype "output"))
    )
    (net (code "152") (name "unconnected-(IC7-P1_2{slash}SCL-Pad13)") (class "Default")
      (node (ref "IC7") (pin "13") (pinfunction "P1_2/SCL_13") (pintype "bidirectional"))
    )
    (net (code "153") (name "unconnected-(IC7-P1_2{slash}SDA-Pad14)") (class "Default")
      (node (ref "IC7") (pin "14") (pinfunction "P1_2/SDA_14") (pintype "bidirectional"))
    )
    (net (code "154") (name "unconnected-(IC7-P2_2-Pad5)") (class "Default")
      (node (ref "IC7") (pin "5") (pinfunction "P2_2_5") (pintype "bidirectional"))
    )
    (net (code "155") (name "unconnected-(IC7-P2_3-Pad9)") (class "Default")
      (node (ref "IC7") (pin "9") (pinfunction "P2_3_9") (pintype "bidirectional"))
    )
    (net (code "156") (name "unconnected-(IC7-P2_4-Pad19)") (class "Default")
      (node (ref "IC7") (pin "19") (pinfunction "P2_4_19") (pintype "bidirectional"))
    )
    (net (code "157") (name "unconnected-(IC7-P3_5-Pad28)") (class "Default")
      (node (ref "IC7") (pin "28") (pinfunction "P3_5_28") (pintype "output"))
    )
    (net (code "158") (name "unconnected-(IC7-ULPC_O-Pad8)") (class "Default")
      (node (ref "IC7") (pin "8") (pinfunction "ULPC_O_8") (pintype "output"))
    )
    (net (code "159") (name "unconnected-(IC8-PA8-Pad26)") (class "Default")
      (node (ref "IC8") (pin "26") (pinfunction "PA8_26") (pintype "bidirectional"))
    )
    (net (code "160") (name "unconnected-(IC8-PA23-Pad73)") (class "Default")
      (node (ref "IC8") (pin "73") (pinfunction "PA23_73") (pintype "bidirectional"))
    )
    (net (code "161") (name "unconnected-(IC8-VLCD-Pad38)") (class "Default")
      (node (ref "IC8") (pin "38") (pinfunction "VLCD_38") (pintype "bidirectional"))
    )
    (net (code "162") (name "unconnected-(J2-ID-Pad4)") (class "Default")
      (node (ref "J2") (pin "4") (pinfunction "ID_4") (pintype "bidirectional"))
    )
    (net (code "163") (name "unconnected-(SV1-Pad2)") (class "Default")
      (node (ref "SV1") (pin "2") (pinfunction "2_2") (pintype "passive"))
    )
    (net (code "164") (name "unconnected-(SV1-Pad3)") (class "Default")
      (node (ref "SV1") (pin "3") (pinfunction "3_3") (pintype "passive"))
    )
    (net (code "165") (name "unconnected-(SV1-Pad5)") (class "Default")
      (node (ref "SV1") (pin "5") (pinfunction "5_5") (pintype "passive"))
    )
    (net (code "166") (name "unconnected-(SV1-Pad11)") (class "Default")
      (node (ref "SV1") (pin "11") (pinfunction "11_11") (pintype "passive"))
    )
    (net (code "167") (name "unconnected-(SV1-Pad13)") (class "Default")
      (node (ref "SV1") (pin "13") (pinfunction "13_13") (pintype "passive"))
    )
    (net (code "168") (name "unconnected-(SV1-Pad17)") (class "Default")
      (node (ref "SV1") (pin "17") (pinfunction "17_17") (pintype "passive"))
    )
    (net (code "169") (name "unconnected-(SV1-Pad19)") (class "Default")
      (node (ref "SV1") (pin "19") (pinfunction "19_19") (pintype "passive"))
    )
    (net (code "170") (name "unconnected-(X3-Pad3)") (class "Default")
      (node (ref "X3") (pin "3") (pinfunction "3_3") (pintype "passive"))
    )
    (net (code "171") (name "unconnected-(X3-Pad9)") (class "Default")
      (node (ref "X3") (pin "9") (pinfunction "9_9") (pintype "passive"))
    )
    (net (code "172") (name "unconnected-(X3-Pad15)") (class "Default")
      (node (ref "X3") (pin "15") (pinfunction "15_15") (pintype "passive"))
    )
    (net (code "173") (name "unconnected-(X3-Pad18)") (class "Default")
      (node (ref "X3") (pin "18") (pinfunction "18_18") (pintype "passive"))
    )
    (net (code "174") (name "~{OLED_RESET}") (class "Default")
      (node (ref "IC8") (pin "45") (pinfunction "PC15_45") (pintype "bidirectional"))
      (node (ref "X3") (pin "16") (pinfunction "16_16") (pintype "passive"))
    )
    (net (code "175") (name "~{OLED_SPI_CS}") (class "Default")
      (node (ref "IC8") (pin "48") (pinfunction "PA14_48") (pintype "bidirectional"))
      (node (ref "JP2") (pin "3") (pinfunction "3_3") (pintype "passive"))
      (node (ref "X3") (pin "17") (pinfunction "17_17") (pintype "passive"))
    )
    (net (code "176") (name "~{PG}_TRANS") (class "Default")
      (node (ref "IC6") (pin "2") (pinfunction "I/OVL1_2") (pintype "bidirectional"))
      (node (ref "IC8") (pin "66") (pinfunction "PB18_66") (pintype "bidirectional"))
    )
    (net (code "177") (name "~{RESET}") (class "Default")
      (node (ref "C15") (pin "1") (pinfunction "1_1") (pintype "passive"))
      (node (ref "IC8") (pin "88") (pinfunction "RESET_88") (pintype "bidirectional"))
      (node (ref "R20") (pin "2") (pinfunction "2_2") (pintype "passive"))
      (node (ref "R23") (pin "1") (pinfunction "1_1") (pintype "passive"))
      (node (ref "SV1") (pin "15") (pinfunction "15_15") (pintype "passive"))
    )
  )
)
